# 8bitBusConcept.net
KiCad netlist of a schematic drawn in EAGLE
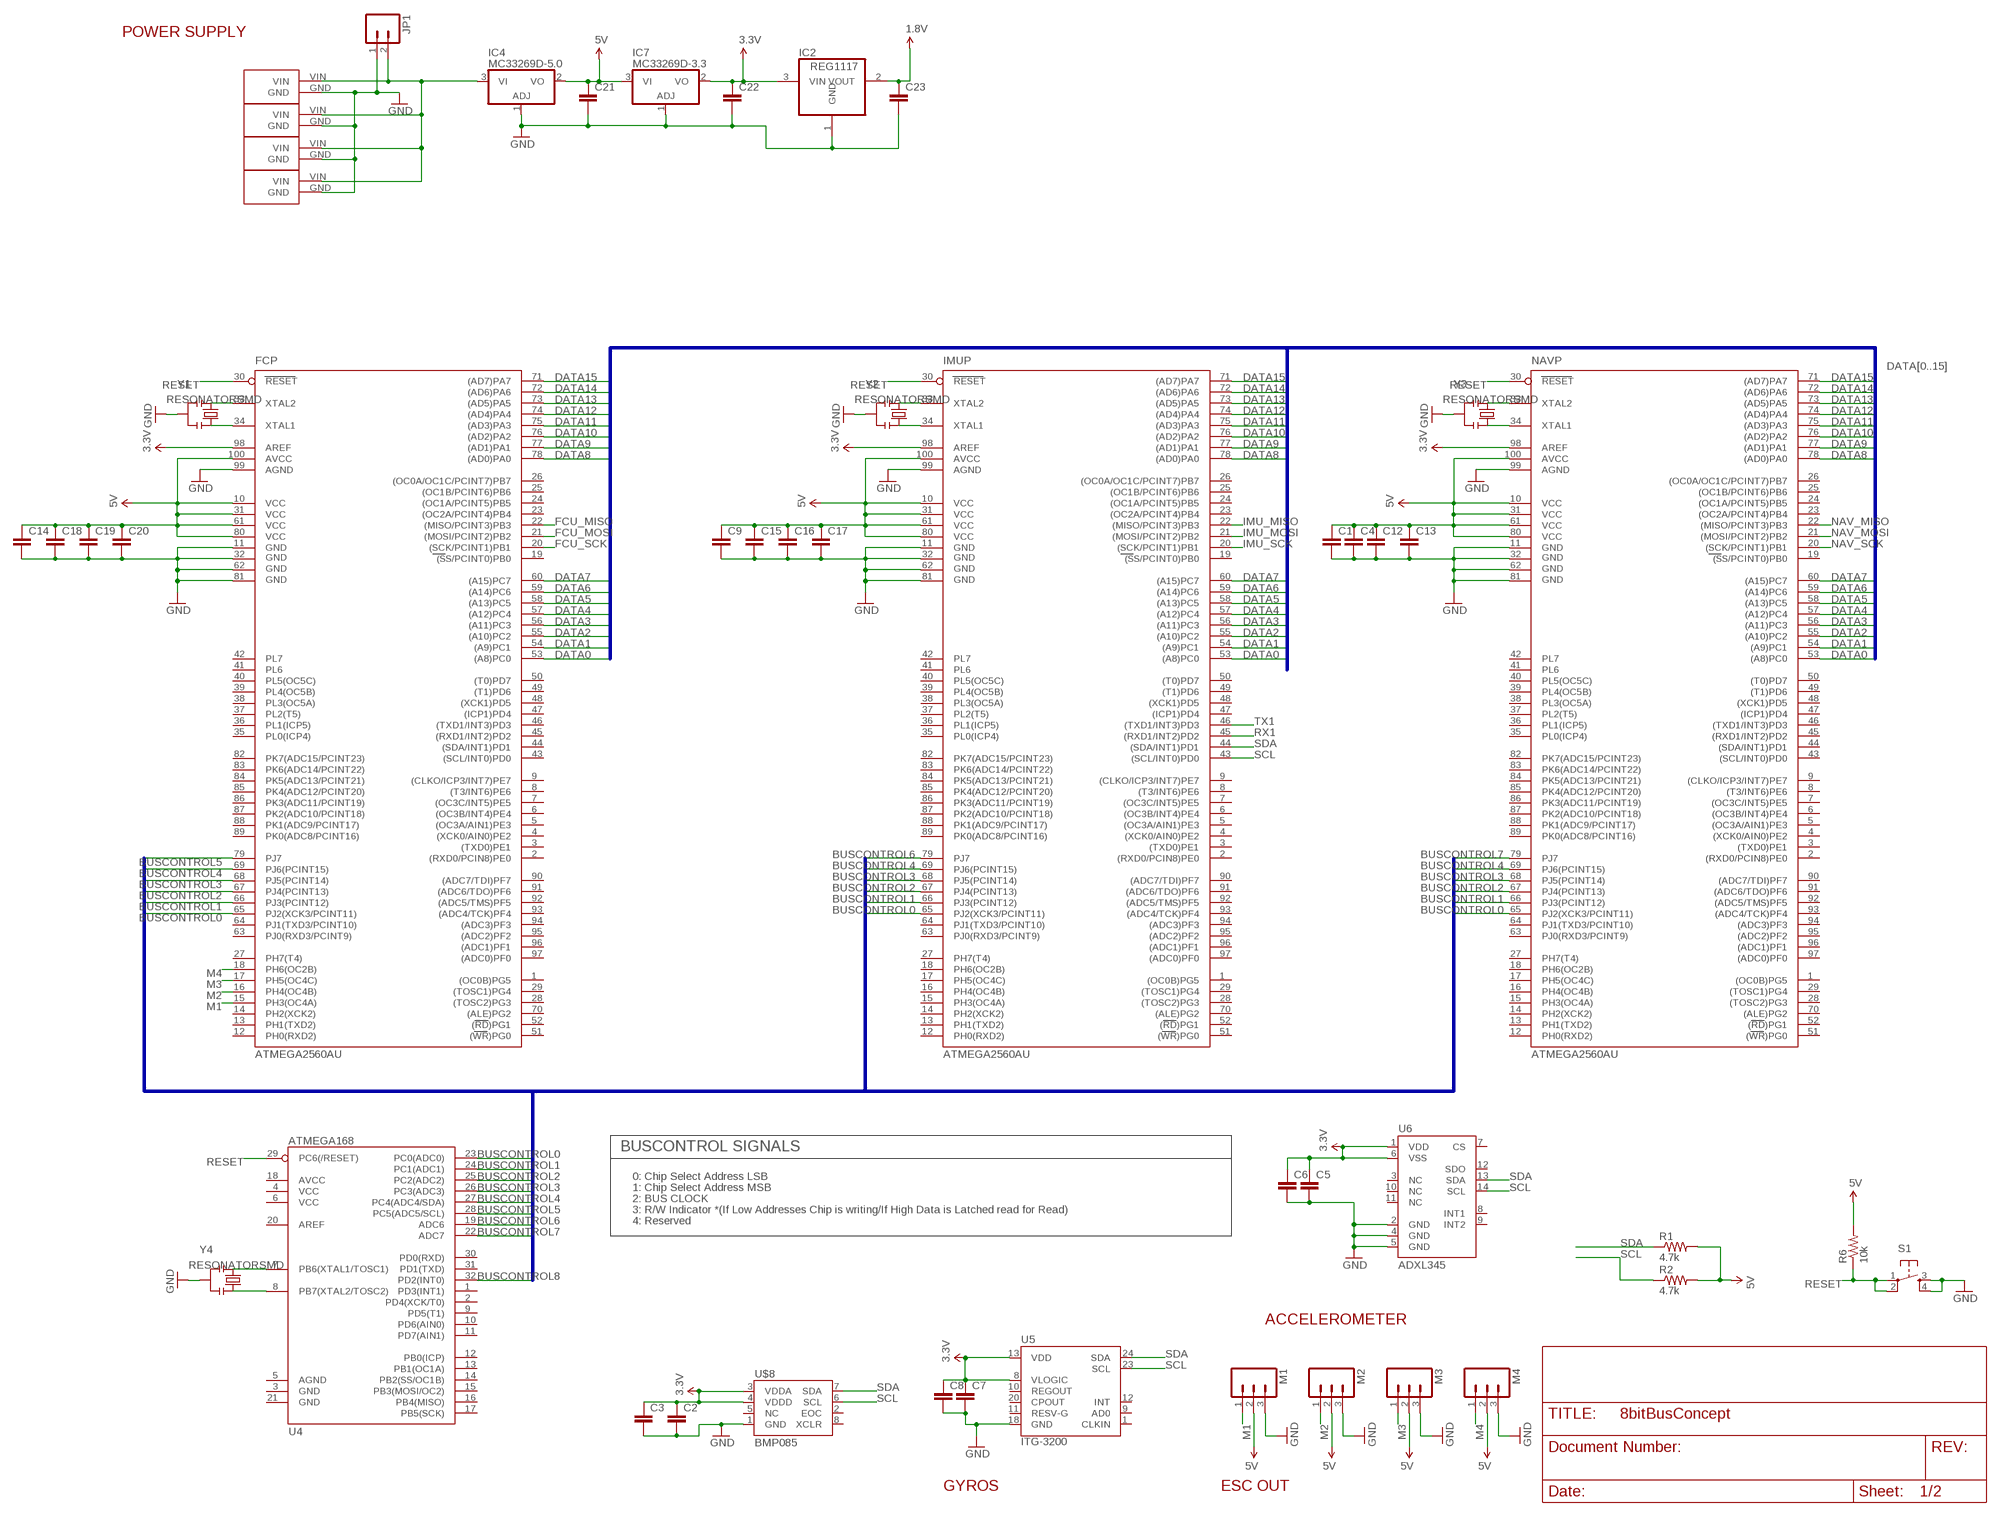
[diagram p0: schematic, sheet 1, part 1 of 2]
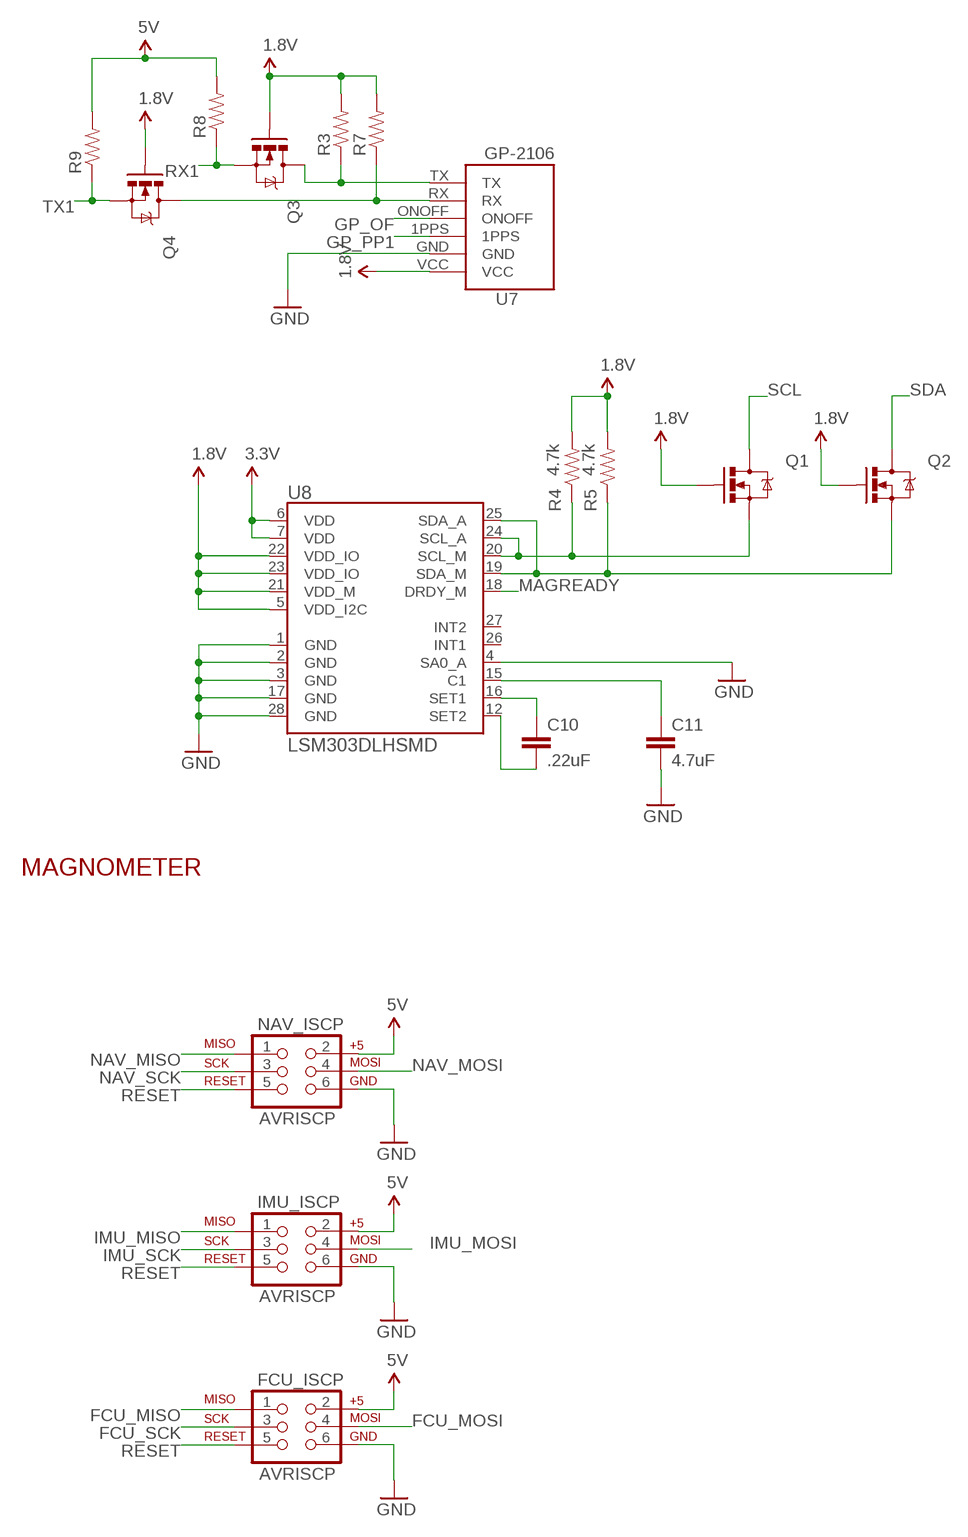
[diagram p1: schematic, sheet 1, part 2 of 2]

(export (version "E")
  (design (tool "Eeschema 10.0.6"))
  (components
    (comp (ref "C1")
      (value "CAP0805")
      (footprint "eagle-import:0805")
      (libsource (lib "eagle-import") (part "CAP0805"))
    )
    (comp (ref "C2")
      (value "CAP0805")
      (footprint "eagle-import:0805")
      (libsource (lib "eagle-import") (part "CAP0805"))
    )
    (comp (ref "C3")
      (value "CAP0805")
      (footprint "eagle-import:0805")
      (libsource (lib "eagle-import") (part "CAP0805"))
    )
    (comp (ref "C4")
      (value "CAP0805")
      (footprint "eagle-import:0805")
      (libsource (lib "eagle-import") (part "CAP0805"))
    )
    (comp (ref "C5")
      (value "CAP0805")
      (footprint "eagle-import:0805")
      (libsource (lib "eagle-import") (part "CAP0805"))
    )
    (comp (ref "C6")
      (value "CAP0805")
      (footprint "eagle-import:0805")
      (libsource (lib "eagle-import") (part "CAP0805"))
    )
    (comp (ref "C7")
      (value "CAP0805")
      (footprint "eagle-import:0805")
      (libsource (lib "eagle-import") (part "CAP0805"))
    )
    (comp (ref "C8")
      (value "CAP0805")
      (footprint "eagle-import:0805")
      (libsource (lib "eagle-import") (part "CAP0805"))
    )
    (comp (ref "C9")
      (value "CAP0805")
      (footprint "eagle-import:0805")
      (libsource (lib "eagle-import") (part "CAP0805"))
    )
    (comp (ref "C10")
      (value ".22uF")
      (footprint "eagle-import:0805")
      (libsource (lib "eagle-import") (part "CAP0805"))
    )
    (comp (ref "C11")
      (value "4.7uF")
      (footprint "eagle-import:0805")
      (libsource (lib "eagle-import") (part "CAP0805"))
    )
    (comp (ref "C12")
      (value "CAP0805")
      (footprint "eagle-import:0805")
      (libsource (lib "eagle-import") (part "CAP0805"))
    )
    (comp (ref "C13")
      (value "CAP0805")
      (footprint "eagle-import:0805")
      (libsource (lib "eagle-import") (part "CAP0805"))
    )
    (comp (ref "C14")
      (value "CAP0805")
      (footprint "eagle-import:0805")
      (libsource (lib "eagle-import") (part "CAP0805"))
    )
    (comp (ref "C15")
      (value "CAP0805")
      (footprint "eagle-import:0805")
      (libsource (lib "eagle-import") (part "CAP0805"))
    )
    (comp (ref "C16")
      (value "CAP0805")
      (footprint "eagle-import:0805")
      (libsource (lib "eagle-import") (part "CAP0805"))
    )
    (comp (ref "C17")
      (value "CAP0805")
      (footprint "eagle-import:0805")
      (libsource (lib "eagle-import") (part "CAP0805"))
    )
    (comp (ref "C18")
      (value "CAP0805")
      (footprint "eagle-import:0805")
      (libsource (lib "eagle-import") (part "CAP0805"))
    )
    (comp (ref "C19")
      (value "CAP0805")
      (footprint "eagle-import:0805")
      (libsource (lib "eagle-import") (part "CAP0805"))
    )
    (comp (ref "C20")
      (value "CAP0805")
      (footprint "eagle-import:0805")
      (libsource (lib "eagle-import") (part "CAP0805"))
    )
    (comp (ref "C21")
      (value "CAP0805")
      (footprint "eagle-import:0805")
      (libsource (lib "eagle-import") (part "CAP0805"))
    )
    (comp (ref "C22")
      (value "CAP0805")
      (footprint "eagle-import:0805")
      (libsource (lib "eagle-import") (part "CAP0805"))
    )
    (comp (ref "C23")
      (value "CAP0805")
      (footprint "eagle-import:0805")
      (libsource (lib "eagle-import") (part "CAP0805"))
    )
    (comp (ref "FCP")
      (value "ATMEGA2560AU")
      (footprint "eagle-import:TQFP100")
      (libsource (lib "eagle-import") (part "ATMEGA2560AU"))
    )
    (comp (ref "FCU_ISCP")
      (value "AVRISCP")
      (footprint "eagle-import:2X3")
      (libsource (lib "eagle-import") (part "AVR_SPI_PRG_6PTH"))
    )
    (comp (ref "IC2")
      (value "REG1117")
      (footprint "eagle-import:SOT223")
      (libsource (lib "eagle-import") (part "REG1117"))
    )
    (comp (ref "IC4")
      (value "MC33269D-5.0")
      (footprint "eagle-import:DPACK")
      (libsource (lib "eagle-import") (part "MC33269?D-5.0"))
    )
    (comp (ref "IC7")
      (value "MC33269D-3.3")
      (footprint "eagle-import:DPACK")
      (libsource (lib "eagle-import") (part "MC33269?D-3.3"))
    )
    (comp (ref "IMUP")
      (value "ATMEGA2560AU")
      (footprint "eagle-import:TQFP100")
      (libsource (lib "eagle-import") (part "ATMEGA2560AU"))
    )
    (comp (ref "IMU_ISCP")
      (value "AVRISCP")
      (footprint "eagle-import:2X3")
      (libsource (lib "eagle-import") (part "AVR_SPI_PRG_6PTH"))
    )
    (comp (ref "JP1")
      (value "M02PTH4")
      (footprint "eagle-import:1X02_XTRA_BIG")
      (libsource (lib "eagle-import") (part "M02PTH4"))
    )
    (comp (ref "M1")
      (value "M03PTH")
      (footprint "eagle-import:1X03")
      (libsource (lib "eagle-import") (part "M03PTH"))
    )
    (comp (ref "M2")
      (value "M03PTH")
      (footprint "eagle-import:1X03")
      (libsource (lib "eagle-import") (part "M03PTH"))
    )
    (comp (ref "M3")
      (value "M03PTH")
      (footprint "eagle-import:1X03")
      (libsource (lib "eagle-import") (part "M03PTH"))
    )
    (comp (ref "M4")
      (value "M03PTH")
      (footprint "eagle-import:1X03")
      (libsource (lib "eagle-import") (part "M03PTH"))
    )
    (comp (ref "NAVP")
      (value "ATMEGA2560AU")
      (footprint "eagle-import:TQFP100")
      (libsource (lib "eagle-import") (part "ATMEGA2560AU"))
    )
    (comp (ref "NAV_ISCP")
      (value "AVRISCP")
      (footprint "eagle-import:2X3")
      (libsource (lib "eagle-import") (part "AVR_SPI_PRG_6PTH"))
    )
    (comp (ref "Q1")
      (value "MOSFET-NCHANNELSMD")
      (footprint "eagle-import:SOT23-3")
      (libsource (lib "eagle-import") (part "MOSFET-NCHANNELSMD"))
    )
    (comp (ref "Q2")
      (value "MOSFET-NCHANNELSMD")
      (footprint "eagle-import:SOT23-3")
      (libsource (lib "eagle-import") (part "MOSFET-NCHANNELSMD"))
    )
    (comp (ref "Q3")
      (value "MOSFET-NCHANNELSMD")
      (footprint "eagle-import:SOT23-3")
      (libsource (lib "eagle-import") (part "MOSFET-NCHANNELSMD"))
    )
    (comp (ref "Q4")
      (value "MOSFET-NCHANNELSMD")
      (footprint "eagle-import:SOT23-3")
      (libsource (lib "eagle-import") (part "MOSFET-NCHANNELSMD"))
    )
    (comp (ref "R1")
      (value "4.7k")
      (footprint "eagle-import:0805")
      (libsource (lib "eagle-import") (part "RESISTOR0805-RES"))
    )
    (comp (ref "R2")
      (value "4.7k")
      (footprint "eagle-import:0805")
      (libsource (lib "eagle-import") (part "RESISTOR0805-RES"))
    )
    (comp (ref "R3")
      (value "RESISTOR0805-RES")
      (footprint "eagle-import:0805")
      (libsource (lib "eagle-import") (part "RESISTOR0805-RES"))
    )
    (comp (ref "R4")
      (value "4.7k")
      (footprint "eagle-import:0805")
      (libsource (lib "eagle-import") (part "RESISTOR0805-RES"))
    )
    (comp (ref "R5")
      (value "4.7k")
      (footprint "eagle-import:0805")
      (libsource (lib "eagle-import") (part "RESISTOR0805-RES"))
    )
    (comp (ref "R6")
      (value "10k")
      (footprint "eagle-import:0805")
      (libsource (lib "eagle-import") (part "RESISTOR0805-RES"))
    )
    (comp (ref "R7")
      (value "RESISTOR0805-RES")
      (footprint "eagle-import:0805")
      (libsource (lib "eagle-import") (part "RESISTOR0805-RES"))
    )
    (comp (ref "R8")
      (value "RESISTOR0805-RES")
      (footprint "eagle-import:0805")
      (libsource (lib "eagle-import") (part "RESISTOR0805-RES"))
    )
    (comp (ref "R9")
      (value "RESISTOR0805-RES")
      (footprint "eagle-import:0805")
      (libsource (lib "eagle-import") (part "RESISTOR0805-RES"))
    )
    (comp (ref "S1")
      (value "TAC_SWITCHSMD")
      (footprint "eagle-import:TACTILE_SWITCH_SMD")
      (libsource (lib "eagle-import") (part "TAC_SWITCHSMD"))
    )
    (comp (ref "U$8")
      (value "BMP085")
      (footprint "eagle-import:BMP085")
      (libsource (lib "eagle-import") (part "BMP085"))
    )
    (comp (ref "U$24")
      (value "ESC_POWER")
      (footprint "eagle-import:ESCPOWER")
      (libsource (lib "eagle-import") (part "ESC_POWER"))
    )
    (comp (ref "U$25")
      (value "ESC_POWER")
      (footprint "eagle-import:ESCPOWER")
      (libsource (lib "eagle-import") (part "ESC_POWER"))
    )
    (comp (ref "U$26")
      (value "ESC_POWER")
      (footprint "eagle-import:ESCPOWER")
      (libsource (lib "eagle-import") (part "ESC_POWER"))
    )
    (comp (ref "U$27")
      (value "ESC_POWER")
      (footprint "eagle-import:ESCPOWER")
      (libsource (lib "eagle-import") (part "ESC_POWER"))
    )
    (comp (ref "U4")
      (value "ATMEGA168")
      (footprint "eagle-import:TQFP32-08")
      (libsource (lib "eagle-import") (part "ATMEGA168"))
    )
    (comp (ref "U5")
      (value "ITG-3200")
      (footprint "eagle-import:QFN-24")
      (libsource (lib "eagle-import") (part "ITG-3200"))
    )
    (comp (ref "U6")
      (value "ADXL345")
      (footprint "eagle-import:LGA14")
      (libsource (lib "eagle-import") (part "ADXL345"))
    )
    (comp (ref "U7")
      (value "GP-2106")
      (footprint "eagle-import:GP-2106")
      (libsource (lib "eagle-import") (part "GP-2106"))
    )
    (comp (ref "U8")
      (value "LSM303DLHSMD")
      (footprint "eagle-import:LGA28-5X5")
      (libsource (lib "eagle-import") (part "LSM303DLHSMD"))
    )
    (comp (ref "Y1")
      (value "RESONATORSMD")
      (footprint "eagle-import:RESONATOR-SMD")
      (libsource (lib "eagle-import") (part "RESONATORSMD"))
    )
    (comp (ref "Y2")
      (value "RESONATORSMD")
      (footprint "eagle-import:RESONATOR-SMD")
      (libsource (lib "eagle-import") (part "RESONATORSMD"))
    )
    (comp (ref "Y3")
      (value "RESONATORSMD")
      (footprint "eagle-import:RESONATOR-SMD")
      (libsource (lib "eagle-import") (part "RESONATORSMD"))
    )
    (comp (ref "Y4")
      (value "RESONATORSMD")
      (footprint "eagle-import:RESONATOR-SMD")
      (libsource (lib "eagle-import") (part "RESONATORSMD"))
    )
  )
  (nets
    (net (code "2") (name "1.8V") (class "Default")
      (node (ref "C23") (pin "1") (pinfunction "1_1") (pintype "passive"))
      (node (ref "IC2") (pin "2") (pinfunction "VOUT_2") (pintype "output"))
      (node (ref "Q1") (pin "1") (pinfunction "G_1") (pintype "passive"))
      (node (ref "Q2") (pin "1") (pinfunction "G_1") (pintype "passive"))
      (node (ref "Q3") (pin "1") (pinfunction "G_1") (pintype "passive"))
      (node (ref "Q4") (pin "1") (pinfunction "G_1") (pintype "passive"))
      (node (ref "R3") (pin "2") (pinfunction "2_2") (pintype "passive"))
      (node (ref "R4") (pin "2") (pinfunction "2_2") (pintype "passive"))
      (node (ref "R5") (pin "2") (pinfunction "2_2") (pintype "passive"))
      (node (ref "R7") (pin "2") (pinfunction "2_2") (pintype "passive"))
      (node (ref "U7") (pin "VCC") (pinfunction "VCC_VCC") (pintype "bidirectional"))
      (node (ref "U8") (pin "21") (pinfunction "VDD_M_21") (pintype "bidirectional"))
      (node (ref "U8") (pin "22") (pinfunction "VDD_IO_22") (pintype "bidirectional"))
      (node (ref "U8") (pin "23") (pinfunction "VDD_IO_23") (pintype "bidirectional"))
      (node (ref "U8") (pin "5") (pinfunction "VDD_I2C_5") (pintype "bidirectional"))
    )
    (net (code "3") (name "3.3V") (class "Default")
      (node (ref "C2") (pin "1") (pinfunction "1_1") (pintype "passive"))
      (node (ref "C22") (pin "1") (pinfunction "1_1") (pintype "passive"))
      (node (ref "C3") (pin "1") (pinfunction "1_1") (pintype "passive"))
      (node (ref "C5") (pin "1") (pinfunction "1_1") (pintype "passive"))
      (node (ref "C6") (pin "1") (pinfunction "1_1") (pintype "passive"))
      (node (ref "C7") (pin "1") (pinfunction "1_1") (pintype "passive"))
      (node (ref "C8") (pin "1") (pinfunction "1_1") (pintype "passive"))
      (node (ref "FCP") (pin "98") (pinfunction "AREF_98") (pintype "bidirectional"))
      (node (ref "IC2") (pin "3") (pinfunction "VIN_3") (pintype "input"))
      (node (ref "IC7") (pin "2") (pinfunction "VO_2") (pintype "passive"))
      (node (ref "IMUP") (pin "98") (pinfunction "AREF_98") (pintype "bidirectional"))
      (node (ref "NAVP") (pin "98") (pinfunction "AREF_98") (pintype "bidirectional"))
      (node (ref "U$8") (pin "3") (pinfunction "VDDA_3") (pintype "power_in"))
      (node (ref "U$8") (pin "4") (pinfunction "VDDD_4") (pintype "power_in"))
      (node (ref "U5") (pin "13") (pinfunction "VDD_13") (pintype "bidirectional"))
      (node (ref "U5") (pin "8") (pinfunction "VLOGIC_8") (pintype "bidirectional"))
      (node (ref "U6") (pin "1") (pinfunction "VDD_1") (pintype "bidirectional"))
      (node (ref "U6") (pin "6") (pinfunction "VSS_6") (pintype "bidirectional"))
      (node (ref "U8") (pin "6") (pinfunction "VDD_6") (pintype "bidirectional"))
      (node (ref "U8") (pin "7") (pinfunction "VDD_7") (pintype "bidirectional"))
    )
    (net (code "4") (name "5V") (class "Default")
      (node (ref "C1") (pin "1") (pinfunction "1_1") (pintype "passive"))
      (node (ref "C12") (pin "1") (pinfunction "1_1") (pintype "passive"))
      (node (ref "C13") (pin "1") (pinfunction "1_1") (pintype "passive"))
      (node (ref "C14") (pin "1") (pinfunction "1_1") (pintype "passive"))
      (node (ref "C15") (pin "1") (pinfunction "1_1") (pintype "passive"))
      (node (ref "C16") (pin "1") (pinfunction "1_1") (pintype "passive"))
      (node (ref "C17") (pin "1") (pinfunction "1_1") (pintype "passive"))
      (node (ref "C18") (pin "1") (pinfunction "1_1") (pintype "passive"))
      (node (ref "C19") (pin "1") (pinfunction "1_1") (pintype "passive"))
      (node (ref "C20") (pin "1") (pinfunction "1_1") (pintype "passive"))
      (node (ref "C21") (pin "1") (pinfunction "1_1") (pintype "passive"))
      (node (ref "C4") (pin "1") (pinfunction "1_1") (pintype "passive"))
      (node (ref "C9") (pin "1") (pinfunction "1_1") (pintype "passive"))
      (node (ref "FCP") (pin "10") (pinfunction "VCC_10") (pintype "power_in"))
      (node (ref "FCP") (pin "100") (pinfunction "AVCC_100") (pintype "power_in"))
      (node (ref "FCP") (pin "31") (pinfunction "VCC1_31") (pintype "power_in"))
      (node (ref "FCP") (pin "61") (pinfunction "VCC2_61") (pintype "power_in"))
      (node (ref "FCP") (pin "80") (pinfunction "VCC3_80") (pintype "power_in"))
      (node (ref "FCU_ISCP") (pin "2") (pinfunction "2_2") (pintype "passive"))
      (node (ref "IC4") (pin "2") (pinfunction "VO_2") (pintype "passive"))
      (node (ref "IC7") (pin "3") (pinfunction "VI_3") (pintype "input"))
      (node (ref "IMUP") (pin "10") (pinfunction "VCC_10") (pintype "power_in"))
      (node (ref "IMUP") (pin "100") (pinfunction "AVCC_100") (pintype "power_in"))
      (node (ref "IMUP") (pin "31") (pinfunction "VCC1_31") (pintype "power_in"))
      (node (ref "IMUP") (pin "61") (pinfunction "VCC2_61") (pintype "power_in"))
      (node (ref "IMUP") (pin "80") (pinfunction "VCC3_80") (pintype "power_in"))
      (node (ref "IMU_ISCP") (pin "2") (pinfunction "2_2") (pintype "passive"))
      (node (ref "M1") (pin "2") (pinfunction "2_2") (pintype "passive"))
      (node (ref "M2") (pin "2") (pinfunction "2_2") (pintype "passive"))
      (node (ref "M3") (pin "2") (pinfunction "2_2") (pintype "passive"))
      (node (ref "M4") (pin "2") (pinfunction "2_2") (pintype "passive"))
      (node (ref "NAVP") (pin "10") (pinfunction "VCC_10") (pintype "power_in"))
      (node (ref "NAVP") (pin "100") (pinfunction "AVCC_100") (pintype "power_in"))
      (node (ref "NAVP") (pin "31") (pinfunction "VCC1_31") (pintype "power_in"))
      (node (ref "NAVP") (pin "61") (pinfunction "VCC2_61") (pintype "power_in"))
      (node (ref "NAVP") (pin "80") (pinfunction "VCC3_80") (pintype "power_in"))
      (node (ref "NAV_ISCP") (pin "2") (pinfunction "2_2") (pintype "passive"))
      (node (ref "R1") (pin "2") (pinfunction "2_2") (pintype "passive"))
      (node (ref "R2") (pin "2") (pinfunction "2_2") (pintype "passive"))
      (node (ref "R6") (pin "2") (pinfunction "2_2") (pintype "passive"))
      (node (ref "R8") (pin "2") (pinfunction "2_2") (pintype "passive"))
      (node (ref "R9") (pin "2") (pinfunction "2_2") (pintype "passive"))
    )
    (net (code "5") (name "BUSCONTROL0") (class "Default")
      (node (ref "FCP") (pin "65") (pinfunction "PJ2(XCK3/PCINT11)_65") (pintype "bidirectional"))
      (node (ref "IMUP") (pin "65") (pinfunction "PJ2(XCK3/PCINT11)_65") (pintype "bidirectional"))
      (node (ref "NAVP") (pin "65") (pinfunction "PJ2(XCK3/PCINT11)_65") (pintype "bidirectional"))
      (node (ref "U4") (pin "23") (pinfunction "PC0(ADC0)_23") (pintype "bidirectional"))
    )
    (net (code "6") (name "BUSCONTROL1") (class "Default")
      (node (ref "FCP") (pin "66") (pinfunction "PJ3(PCINT12)_66") (pintype "bidirectional"))
      (node (ref "IMUP") (pin "66") (pinfunction "PJ3(PCINT12)_66") (pintype "bidirectional"))
      (node (ref "NAVP") (pin "66") (pinfunction "PJ3(PCINT12)_66") (pintype "bidirectional"))
      (node (ref "U4") (pin "24") (pinfunction "PC1(ADC1)_24") (pintype "bidirectional"))
    )
    (net (code "7") (name "BUSCONTROL2") (class "Default")
      (node (ref "FCP") (pin "67") (pinfunction "PJ4(PCINT13)_67") (pintype "bidirectional"))
      (node (ref "IMUP") (pin "67") (pinfunction "PJ4(PCINT13)_67") (pintype "bidirectional"))
      (node (ref "NAVP") (pin "67") (pinfunction "PJ4(PCINT13)_67") (pintype "bidirectional"))
      (node (ref "U4") (pin "25") (pinfunction "PC2(ADC2)_25") (pintype "bidirectional"))
    )
    (net (code "8") (name "BUSCONTROL3") (class "Default")
      (node (ref "FCP") (pin "68") (pinfunction "PJ5(PCINT14)_68") (pintype "bidirectional"))
      (node (ref "IMUP") (pin "68") (pinfunction "PJ5(PCINT14)_68") (pintype "bidirectional"))
      (node (ref "NAVP") (pin "68") (pinfunction "PJ5(PCINT14)_68") (pintype "bidirectional"))
      (node (ref "U4") (pin "26") (pinfunction "PC3(ADC3)_26") (pintype "bidirectional"))
    )
    (net (code "9") (name "BUSCONTROL4") (class "Default")
      (node (ref "FCP") (pin "69") (pinfunction "PJ6(PCINT15)_69") (pintype "bidirectional"))
      (node (ref "IMUP") (pin "69") (pinfunction "PJ6(PCINT15)_69") (pintype "bidirectional"))
      (node (ref "NAVP") (pin "69") (pinfunction "PJ6(PCINT15)_69") (pintype "bidirectional"))
      (node (ref "U4") (pin "27") (pinfunction "PC4(ADC4/SDA)_27") (pintype "bidirectional"))
    )
    (net (code "10") (name "BUSCONTROL5") (class "Default")
      (node (ref "FCP") (pin "79") (pinfunction "PJ7_79") (pintype "bidirectional"))
      (node (ref "U4") (pin "28") (pinfunction "PC5(ADC5/SCL)_28") (pintype "bidirectional"))
    )
    (net (code "11") (name "BUSCONTROL6") (class "Default")
      (node (ref "IMUP") (pin "79") (pinfunction "PJ7_79") (pintype "bidirectional"))
      (node (ref "U4") (pin "19") (pinfunction "ADC6_19") (pintype "bidirectional"))
    )
    (net (code "12") (name "BUSCONTROL7") (class "Default")
      (node (ref "NAVP") (pin "79") (pinfunction "PJ7_79") (pintype "bidirectional"))
      (node (ref "U4") (pin "22") (pinfunction "ADC7_22") (pintype "bidirectional"))
    )
    (net (code "13") (name "BUSCONTROL8") (class "Default")
      (node (ref "U4") (pin "32") (pinfunction "PD2(INT0)_32") (pintype "bidirectional"))
    )
    (net (code "14") (name "DATA0") (class "Default")
      (node (ref "FCP") (pin "53") (pinfunction "(A8)PC0_53") (pintype "bidirectional"))
      (node (ref "IMUP") (pin "53") (pinfunction "(A8)PC0_53") (pintype "bidirectional"))
      (node (ref "NAVP") (pin "53") (pinfunction "(A8)PC0_53") (pintype "bidirectional"))
    )
    (net (code "15") (name "DATA1") (class "Default")
      (node (ref "FCP") (pin "54") (pinfunction "(A9)PC1_54") (pintype "bidirectional"))
      (node (ref "IMUP") (pin "54") (pinfunction "(A9)PC1_54") (pintype "bidirectional"))
      (node (ref "NAVP") (pin "54") (pinfunction "(A9)PC1_54") (pintype "bidirectional"))
    )
    (net (code "16") (name "DATA2") (class "Default")
      (node (ref "FCP") (pin "55") (pinfunction "(A10)PC2_55") (pintype "bidirectional"))
      (node (ref "IMUP") (pin "55") (pinfunction "(A10)PC2_55") (pintype "bidirectional"))
      (node (ref "NAVP") (pin "55") (pinfunction "(A10)PC2_55") (pintype "bidirectional"))
    )
    (net (code "17") (name "DATA3") (class "Default")
      (node (ref "FCP") (pin "56") (pinfunction "(A11)PC3_56") (pintype "bidirectional"))
      (node (ref "IMUP") (pin "56") (pinfunction "(A11)PC3_56") (pintype "bidirectional"))
      (node (ref "NAVP") (pin "56") (pinfunction "(A11)PC3_56") (pintype "bidirectional"))
    )
    (net (code "18") (name "DATA4") (class "Default")
      (node (ref "FCP") (pin "57") (pinfunction "(A12)PC4_57") (pintype "bidirectional"))
      (node (ref "IMUP") (pin "57") (pinfunction "(A12)PC4_57") (pintype "bidirectional"))
      (node (ref "NAVP") (pin "57") (pinfunction "(A12)PC4_57") (pintype "bidirectional"))
    )
    (net (code "19") (name "DATA5") (class "Default")
      (node (ref "FCP") (pin "58") (pinfunction "(A13)PC5_58") (pintype "bidirectional"))
      (node (ref "IMUP") (pin "58") (pinfunction "(A13)PC5_58") (pintype "bidirectional"))
      (node (ref "NAVP") (pin "58") (pinfunction "(A13)PC5_58") (pintype "bidirectional"))
    )
    (net (code "20") (name "DATA6") (class "Default")
      (node (ref "FCP") (pin "59") (pinfunction "(A14)PC6_59") (pintype "bidirectional"))
      (node (ref "IMUP") (pin "59") (pinfunction "(A14)PC6_59") (pintype "bidirectional"))
      (node (ref "NAVP") (pin "59") (pinfunction "(A14)PC6_59") (pintype "bidirectional"))
    )
    (net (code "21") (name "DATA7") (class "Default")
      (node (ref "FCP") (pin "60") (pinfunction "(A15)PC7_60") (pintype "bidirectional"))
      (node (ref "IMUP") (pin "60") (pinfunction "(A15)PC7_60") (pintype "bidirectional"))
      (node (ref "NAVP") (pin "60") (pinfunction "(A15)PC7_60") (pintype "bidirectional"))
    )
    (net (code "22") (name "DATA8") (class "Default")
      (node (ref "FCP") (pin "78") (pinfunction "(AD0)PA0_78") (pintype "bidirectional"))
      (node (ref "IMUP") (pin "78") (pinfunction "(AD0)PA0_78") (pintype "bidirectional"))
      (node (ref "NAVP") (pin "78") (pinfunction "(AD0)PA0_78") (pintype "bidirectional"))
    )
    (net (code "23") (name "DATA9") (class "Default")
      (node (ref "FCP") (pin "77") (pinfunction "(AD1)PA1_77") (pintype "bidirectional"))
      (node (ref "IMUP") (pin "77") (pinfunction "(AD1)PA1_77") (pintype "bidirectional"))
      (node (ref "NAVP") (pin "77") (pinfunction "(AD1)PA1_77") (pintype "bidirectional"))
    )
    (net (code "24") (name "DATA10") (class "Default")
      (node (ref "FCP") (pin "76") (pinfunction "(AD2)PA2_76") (pintype "bidirectional"))
      (node (ref "IMUP") (pin "76") (pinfunction "(AD2)PA2_76") (pintype "bidirectional"))
      (node (ref "NAVP") (pin "76") (pinfunction "(AD2)PA2_76") (pintype "bidirectional"))
    )
    (net (code "25") (name "DATA11") (class "Default")
      (node (ref "FCP") (pin "75") (pinfunction "(AD3)PA3_75") (pintype "bidirectional"))
      (node (ref "IMUP") (pin "75") (pinfunction "(AD3)PA3_75") (pintype "bidirectional"))
      (node (ref "NAVP") (pin "75") (pinfunction "(AD3)PA3_75") (pintype "bidirectional"))
    )
    (net (code "26") (name "DATA12") (class "Default")
      (node (ref "FCP") (pin "74") (pinfunction "(AD4)PA4_74") (pintype "bidirectional"))
      (node (ref "IMUP") (pin "74") (pinfunction "(AD4)PA4_74") (pintype "bidirectional"))
      (node (ref "NAVP") (pin "74") (pinfunction "(AD4)PA4_74") (pintype "bidirectional"))
    )
    (net (code "27") (name "DATA13") (class "Default")
      (node (ref "FCP") (pin "73") (pinfunction "(AD5)PA5_73") (pintype "bidirectional"))
      (node (ref "IMUP") (pin "73") (pinfunction "(AD5)PA5_73") (pintype "bidirectional"))
      (node (ref "NAVP") (pin "73") (pinfunction "(AD5)PA5_73") (pintype "bidirectional"))
    )
    (net (code "28") (name "DATA14") (class "Default")
      (node (ref "FCP") (pin "72") (pinfunction "(AD6)PA6_72") (pintype "bidirectional"))
      (node (ref "IMUP") (pin "72") (pinfunction "(AD6)PA6_72") (pintype "bidirectional"))
      (node (ref "NAVP") (pin "72") (pinfunction "(AD6)PA6_72") (pintype "bidirectional"))
    )
    (net (code "29") (name "DATA15") (class "Default")
      (node (ref "FCP") (pin "71") (pinfunction "(AD7)PA7_71") (pintype "bidirectional"))
      (node (ref "IMUP") (pin "71") (pinfunction "(AD7)PA7_71") (pintype "bidirectional"))
      (node (ref "NAVP") (pin "71") (pinfunction "(AD7)PA7_71") (pintype "bidirectional"))
    )
    (net (code "30") (name "FCU_MISO") (class "Default")
      (node (ref "FCP") (pin "22") (pinfunction "(MISO/PCINT3)PB3_22") (pintype "bidirectional"))
      (node (ref "FCU_ISCP") (pin "1") (pinfunction "1_1") (pintype "passive"))
    )
    (net (code "31") (name "FCU_MOSI") (class "Default")
      (node (ref "FCP") (pin "21") (pinfunction "(MOSI/PCINT2)PB2_21") (pintype "bidirectional"))
      (node (ref "FCU_ISCP") (pin "4") (pinfunction "4_4") (pintype "passive"))
    )
    (net (code "32") (name "FCU_SCK") (class "Default")
      (node (ref "FCP") (pin "20") (pinfunction "(SCK/PCINT1)PB1_20") (pintype "bidirectional"))
      (node (ref "FCU_ISCP") (pin "3") (pinfunction "3_3") (pintype "passive"))
    )
    (net (code "33") (name "GND") (class "Default")
      (node (ref "C1") (pin "2") (pinfunction "2_2") (pintype "passive"))
      (node (ref "C11") (pin "2") (pinfunction "2_2") (pintype "passive"))
      (node (ref "C12") (pin "2") (pinfunction "2_2") (pintype "passive"))
      (node (ref "C13") (pin "2") (pinfunction "2_2") (pintype "passive"))
      (node (ref "C14") (pin "2") (pinfunction "2_2") (pintype "passive"))
      (node (ref "C15") (pin "2") (pinfunction "2_2") (pintype "passive"))
      (node (ref "C16") (pin "2") (pinfunction "2_2") (pintype "passive"))
      (node (ref "C17") (pin "2") (pinfunction "2_2") (pintype "passive"))
      (node (ref "C18") (pin "2") (pinfunction "2_2") (pintype "passive"))
      (node (ref "C19") (pin "2") (pinfunction "2_2") (pintype "passive"))
      (node (ref "C2") (pin "2") (pinfunction "2_2") (pintype "passive"))
      (node (ref "C20") (pin "2") (pinfunction "2_2") (pintype "passive"))
      (node (ref "C21") (pin "2") (pinfunction "2_2") (pintype "passive"))
      (node (ref "C22") (pin "2") (pinfunction "2_2") (pintype "passive"))
      (node (ref "C23") (pin "2") (pinfunction "2_2") (pintype "passive"))
      (node (ref "C3") (pin "2") (pinfunction "2_2") (pintype "passive"))
      (node (ref "C4") (pin "2") (pinfunction "2_2") (pintype "passive"))
      (node (ref "C5") (pin "2") (pinfunction "2_2") (pintype "passive"))
      (node (ref "C6") (pin "2") (pinfunction "2_2") (pintype "passive"))
      (node (ref "C7") (pin "2") (pinfunction "2_2") (pintype "passive"))
      (node (ref "C8") (pin "2") (pinfunction "2_2") (pintype "passive"))
      (node (ref "C9") (pin "2") (pinfunction "2_2") (pintype "passive"))
      (node (ref "FCP") (pin "11") (pinfunction "GND_11") (pintype "power_in"))
      (node (ref "FCP") (pin "32") (pinfunction "GND1_32") (pintype "power_in"))
      (node (ref "FCP") (pin "62") (pinfunction "GND2_62") (pintype "power_in"))
      (node (ref "FCP") (pin "81") (pinfunction "GND3_81") (pintype "power_in"))
      (node (ref "FCP") (pin "99") (pinfunction "AGND_99") (pintype "power_in"))
      (node (ref "FCU_ISCP") (pin "6") (pinfunction "6_6") (pintype "passive"))
      (node (ref "IC2") (pin "1") (pinfunction "GND_1") (pintype "power_in"))
      (node (ref "IC4") (pin "1") (pinfunction "ADJ_1") (pintype "input"))
      (node (ref "IC7") (pin "1") (pinfunction "ADJ_1") (pintype "input"))
      (node (ref "IMUP") (pin "11") (pinfunction "GND_11") (pintype "power_in"))
      (node (ref "IMUP") (pin "32") (pinfunction "GND1_32") (pintype "power_in"))
      (node (ref "IMUP") (pin "62") (pinfunction "GND2_62") (pintype "power_in"))
      (node (ref "IMUP") (pin "81") (pinfunction "GND3_81") (pintype "power_in"))
      (node (ref "IMUP") (pin "99") (pinfunction "AGND_99") (pintype "power_in"))
      (node (ref "IMU_ISCP") (pin "6") (pinfunction "6_6") (pintype "passive"))
      (node (ref "JP1") (pin "1") (pinfunction "1_1") (pintype "passive"))
      (node (ref "M1") (pin "3") (pinfunction "3_3") (pintype "passive"))
      (node (ref "M2") (pin "3") (pinfunction "3_3") (pintype "passive"))
      (node (ref "M3") (pin "3") (pinfunction "3_3") (pintype "passive"))
      (node (ref "M4") (pin "3") (pinfunction "3_3") (pintype "passive"))
      (node (ref "NAVP") (pin "11") (pinfunction "GND_11") (pintype "power_in"))
      (node (ref "NAVP") (pin "32") (pinfunction "GND1_32") (pintype "power_in"))
      (node (ref "NAVP") (pin "62") (pinfunction "GND2_62") (pintype "power_in"))
      (node (ref "NAVP") (pin "81") (pinfunction "GND3_81") (pintype "power_in"))
      (node (ref "NAVP") (pin "99") (pinfunction "AGND_99") (pintype "power_in"))
      (node (ref "NAV_ISCP") (pin "6") (pinfunction "6_6") (pintype "passive"))
      (node (ref "S1") (pin "3") (pinfunction "3_3") (pintype "passive"))
      (node (ref "S1") (pin "4") (pinfunction "4_4") (pintype "passive"))
      (node (ref "U$24") (pin "GND") (pinfunction "GND_GND") (pintype "bidirectional"))
      (node (ref "U$25") (pin "GND") (pinfunction "GND_GND") (pintype "bidirectional"))
      (node (ref "U$26") (pin "GND") (pinfunction "GND_GND") (pintype "bidirectional"))
      (node (ref "U$27") (pin "GND") (pinfunction "GND_GND") (pintype "bidirectional"))
      (node (ref "U$8") (pin "1") (pinfunction "GND_1") (pintype "power_in"))
      (node (ref "U5") (pin "18") (pinfunction "GND_18") (pintype "bidirectional"))
      (node (ref "U6") (pin "2") (pinfunction "GND_2") (pintype "bidirectional"))
      (node (ref "U6") (pin "4") (pinfunction "GND_4") (pintype "bidirectional"))
      (node (ref "U6") (pin "5") (pinfunction "GND_5") (pintype "bidirectional"))
      (node (ref "U7") (pin "GND") (pinfunction "GND_GND") (pintype "bidirectional"))
      (node (ref "U8") (pin "1") (pinfunction "GND_1") (pintype "bidirectional"))
      (node (ref "U8") (pin "17") (pinfunction "GND_17") (pintype "bidirectional"))
      (node (ref "U8") (pin "2") (pinfunction "GND_2") (pintype "bidirectional"))
      (node (ref "U8") (pin "28") (pinfunction "GND_28") (pintype "bidirectional"))
      (node (ref "U8") (pin "3") (pinfunction "GND_3") (pintype "bidirectional"))
      (node (ref "U8") (pin "4") (pinfunction "SA0_A_4") (pintype "bidirectional"))
      (node (ref "Y1") (pin "2") (pinfunction "2_2") (pintype "passive"))
      (node (ref "Y2") (pin "2") (pinfunction "2_2") (pintype "passive"))
      (node (ref "Y3") (pin "2") (pinfunction "2_2") (pintype "passive"))
      (node (ref "Y4") (pin "2") (pinfunction "2_2") (pintype "passive"))
    )
    (net (code "34") (name "GP_OF") (class "Default")
      (node (ref "U7") (pin "ONOFF") (pinfunction "ONOFF_ONOFF") (pintype "bidirectional"))
    )
    (net (code "35") (name "GP_PP1") (class "Default")
      (node (ref "U7") (pin "1PPS") (pinfunction "1PPS_1PPS") (pintype "bidirectional"))
    )
    (net (code "36") (name "IMU_MISO") (class "Default")
      (node (ref "IMUP") (pin "22") (pinfunction "(MISO/PCINT3)PB3_22") (pintype "bidirectional"))
      (node (ref "IMU_ISCP") (pin "1") (pinfunction "1_1") (pintype "passive"))
    )
    (net (code "37") (name "IMU_MOSI") (class "Default")
      (node (ref "IMUP") (pin "21") (pinfunction "(MOSI/PCINT2)PB2_21") (pintype "bidirectional"))
      (node (ref "IMU_ISCP") (pin "4") (pinfunction "4_4") (pintype "passive"))
    )
    (net (code "38") (name "IMU_SCK") (class "Default")
      (node (ref "IMUP") (pin "20") (pinfunction "(SCK/PCINT1)PB1_20") (pintype "bidirectional"))
      (node (ref "IMU_ISCP") (pin "3") (pinfunction "3_3") (pintype "passive"))
    )
    (net (code "39") (name "M1") (class "Default")
      (node (ref "FCP") (pin "15") (pinfunction "PH3(OC4A)_15") (pintype "bidirectional"))
      (node (ref "M1") (pin "1") (pinfunction "1_1") (pintype "passive"))
    )
    (net (code "40") (name "M2") (class "Default")
      (node (ref "FCP") (pin "16") (pinfunction "PH4(OC4B)_16") (pintype "bidirectional"))
      (node (ref "M2") (pin "1") (pinfunction "1_1") (pintype "passive"))
    )
    (net (code "41") (name "M3") (class "Default")
      (node (ref "FCP") (pin "17") (pinfunction "PH5(OC4C)_17") (pintype "bidirectional"))
      (node (ref "M3") (pin "1") (pinfunction "1_1") (pintype "passive"))
    )
    (net (code "42") (name "M4") (class "Default")
      (node (ref "FCP") (pin "18") (pinfunction "PH6(OC2B)_18") (pintype "bidirectional"))
      (node (ref "M4") (pin "1") (pinfunction "1_1") (pintype "passive"))
    )
    (net (code "43") (name "MAGREADY") (class "Default")
      (node (ref "U8") (pin "18") (pinfunction "DRDY_M_18") (pintype "bidirectional"))
    )
    (net (code "44") (name "NAV_MISO") (class "Default")
      (node (ref "NAVP") (pin "22") (pinfunction "(MISO/PCINT3)PB3_22") (pintype "bidirectional"))
      (node (ref "NAV_ISCP") (pin "1") (pinfunction "1_1") (pintype "passive"))
    )
    (net (code "45") (name "NAV_MOSI") (class "Default")
      (node (ref "NAVP") (pin "21") (pinfunction "(MOSI/PCINT2)PB2_21") (pintype "bidirectional"))
      (node (ref "NAV_ISCP") (pin "4") (pinfunction "4_4") (pintype "passive"))
    )
    (net (code "46") (name "NAV_SCK") (class "Default")
      (node (ref "NAVP") (pin "20") (pinfunction "(SCK/PCINT1)PB1_20") (pintype "bidirectional"))
      (node (ref "NAV_ISCP") (pin "3") (pinfunction "3_3") (pintype "passive"))
    )
    (net (code "47") (name "Net-(FCP-XTAL1)") (class "Default")
      (node (ref "FCP") (pin "34") (pinfunction "XTAL1_34") (pintype "input"))
      (node (ref "Y1") (pin "3") (pinfunction "3_3") (pintype "passive"))
    )
    (net (code "48") (name "Net-(FCP-XTAL2)") (class "Default")
      (node (ref "FCP") (pin "33") (pinfunction "XTAL2_33") (pintype "output"))
      (node (ref "Y1") (pin "1") (pinfunction "1_1") (pintype "passive"))
    )
    (net (code "49") (name "Net-(IC4-VI)") (class "Default")
      (node (ref "IC4") (pin "3") (pinfunction "VI_3") (pintype "input"))
      (node (ref "JP1") (pin "2") (pinfunction "2_2") (pintype "passive"))
      (node (ref "U$24") (pin "VIN") (pinfunction "VIN_VIN") (pintype "bidirectional"))
      (node (ref "U$25") (pin "VIN") (pinfunction "VIN_VIN") (pintype "bidirectional"))
      (node (ref "U$26") (pin "VIN") (pinfunction "VIN_VIN") (pintype "bidirectional"))
      (node (ref "U$27") (pin "VIN") (pinfunction "VIN_VIN") (pintype "bidirectional"))
    )
    (net (code "50") (name "Net-(IMUP-XTAL1)") (class "Default")
      (node (ref "IMUP") (pin "34") (pinfunction "XTAL1_34") (pintype "input"))
      (node (ref "Y2") (pin "3") (pinfunction "3_3") (pintype "passive"))
    )
    (net (code "51") (name "Net-(IMUP-XTAL2)") (class "Default")
      (node (ref "IMUP") (pin "33") (pinfunction "XTAL2_33") (pintype "output"))
      (node (ref "Y2") (pin "1") (pinfunction "1_1") (pintype "passive"))
    )
    (net (code "52") (name "Net-(NAVP-XTAL1)") (class "Default")
      (node (ref "NAVP") (pin "34") (pinfunction "XTAL1_34") (pintype "input"))
      (node (ref "Y3") (pin "3") (pinfunction "3_3") (pintype "passive"))
    )
    (net (code "53") (name "Net-(NAVP-XTAL2)") (class "Default")
      (node (ref "NAVP") (pin "33") (pinfunction "XTAL2_33") (pintype "output"))
      (node (ref "Y3") (pin "1") (pinfunction "1_1") (pintype "passive"))
    )
    (net (code "54") (name "Net-(Q1-S)") (class "Default")
      (node (ref "Q1") (pin "2") (pinfunction "S_2") (pintype "passive"))
      (node (ref "R4") (pin "1") (pinfunction "1_1") (pintype "passive"))
      (node (ref "U8") (pin "20") (pinfunction "SCL_M_20") (pintype "bidirectional"))
      (node (ref "U8") (pin "24") (pinfunction "SCL_A_24") (pintype "bidirectional"))
    )
    (net (code "55") (name "Net-(Q2-S)") (class "Default")
      (node (ref "Q2") (pin "2") (pinfunction "S_2") (pintype "passive"))
      (node (ref "R5") (pin "1") (pinfunction "1_1") (pintype "passive"))
      (node (ref "U8") (pin "19") (pinfunction "SDA_M_19") (pintype "bidirectional"))
      (node (ref "U8") (pin "25") (pinfunction "SDA_A_25") (pintype "bidirectional"))
    )
    (net (code "56") (name "Net-(Q3-D)") (class "Default")
      (node (ref "Q3") (pin "3") (pinfunction "D_3") (pintype "passive"))
      (node (ref "R3") (pin "1") (pinfunction "1_1") (pintype "passive"))
      (node (ref "U7") (pin "TX") (pinfunction "TX_TX") (pintype "bidirectional"))
    )
    (net (code "57") (name "Net-(Q4-D)") (class "Default")
      (node (ref "Q4") (pin "3") (pinfunction "D_3") (pintype "passive"))
      (node (ref "R7") (pin "1") (pinfunction "1_1") (pintype "passive"))
      (node (ref "U7") (pin "RX") (pinfunction "RX_RX") (pintype "bidirectional"))
    )
    (net (code "58") (name "Net-(U4-PB6(XTAL1{slash}TOSC1))") (class "Default")
      (node (ref "U4") (pin "7") (pinfunction "PB6(XTAL1/TOSC1)_7") (pintype "bidirectional"))
      (node (ref "Y4") (pin "1") (pinfunction "1_1") (pintype "passive"))
    )
    (net (code "59") (name "Net-(U4-PB7(XTAL2{slash}TOSC2))") (class "Default")
      (node (ref "U4") (pin "8") (pinfunction "PB7(XTAL2/TOSC2)_8") (pintype "bidirectional"))
      (node (ref "Y4") (pin "3") (pinfunction "3_3") (pintype "passive"))
    )
    (net (code "60") (name "Net-(U8-C1)") (class "Default")
      (node (ref "C11") (pin "1") (pinfunction "1_1") (pintype "passive"))
      (node (ref "U8") (pin "15") (pinfunction "C1_15") (pintype "bidirectional"))
    )
    (net (code "61") (name "Net-(U8-SET1)") (class "Default")
      (node (ref "C10") (pin "1") (pinfunction "1_1") (pintype "passive"))
      (node (ref "U8") (pin "16") (pinfunction "SET1_16") (pintype "bidirectional"))
    )
    (net (code "62") (name "Net-(U8-SET2)") (class "Default")
      (node (ref "C10") (pin "2") (pinfunction "2_2") (pintype "passive"))
      (node (ref "U8") (pin "12") (pinfunction "SET2_12") (pintype "bidirectional"))
    )
    (net (code "63") (name "RESET") (class "Default")
      (node (ref "FCP") (pin "30") (pinfunction "RESET_30") (pintype "input"))
      (node (ref "FCU_ISCP") (pin "5") (pinfunction "5_5") (pintype "passive"))
      (node (ref "IMUP") (pin "30") (pinfunction "RESET_30") (pintype "input"))
      (node (ref "IMU_ISCP") (pin "5") (pinfunction "5_5") (pintype "passive"))
      (node (ref "NAVP") (pin "30") (pinfunction "RESET_30") (pintype "input"))
      (node (ref "NAV_ISCP") (pin "5") (pinfunction "5_5") (pintype "passive"))
      (node (ref "R6") (pin "1") (pinfunction "1_1") (pintype "passive"))
      (node (ref "S1") (pin "1") (pinfunction "1_1") (pintype "passive"))
      (node (ref "S1") (pin "2") (pinfunction "2_2") (pintype "passive"))
      (node (ref "U4") (pin "29") (pinfunction "PC6(/RESET)_29") (pintype "bidirectional"))
    )
    (net (code "64") (name "RX1") (class "Default")
      (node (ref "IMUP") (pin "45") (pinfunction "(RXD1/INT2)PD2_45") (pintype "bidirectional"))
      (node (ref "Q3") (pin "2") (pinfunction "S_2") (pintype "passive"))
      (node (ref "R8") (pin "1") (pinfunction "1_1") (pintype "passive"))
    )
    (net (code "65") (name "SCL") (class "Default")
      (node (ref "IMUP") (pin "43") (pinfunction "(SCL/INT0)PD0_43") (pintype "bidirectional"))
      (node (ref "Q1") (pin "3") (pinfunction "D_3") (pintype "passive"))
      (node (ref "R2") (pin "1") (pinfunction "1_1") (pintype "passive"))
      (node (ref "U$8") (pin "6") (pinfunction "SCL_6") (pintype "input"))
      (node (ref "U5") (pin "23") (pinfunction "SCL_23") (pintype "bidirectional"))
      (node (ref "U6") (pin "14") (pinfunction "SCL_14") (pintype "bidirectional"))
    )
    (net (code "66") (name "SDA") (class "Default")
      (node (ref "IMUP") (pin "44") (pinfunction "(SDA/INT1)PD1_44") (pintype "bidirectional"))
      (node (ref "Q2") (pin "3") (pinfunction "D_3") (pintype "passive"))
      (node (ref "R1") (pin "1") (pinfunction "1_1") (pintype "passive"))
      (node (ref "U$8") (pin "7") (pinfunction "SDA_7") (pintype "bidirectional"))
      (node (ref "U5") (pin "24") (pinfunction "SDA_24") (pintype "bidirectional"))
      (node (ref "U6") (pin "13") (pinfunction "SDA_13") (pintype "bidirectional"))
    )
    (net (code "67") (name "TX1") (class "Default")
      (node (ref "IMUP") (pin "46") (pinfunction "(TXD1/INT3)PD3_46") (pintype "bidirectional"))
      (node (ref "Q4") (pin "2") (pinfunction "S_2") (pintype "passive"))
      (node (ref "R9") (pin "1") (pinfunction "1_1") (pintype "passive"))
    )
    (net (code "68") (name "unconnected-(FCP-(ADC0)PF0-Pad97)") (class "Default")
      (node (ref "FCP") (pin "97") (pinfunction "(ADC0)PF0_97") (pintype "bidirectional"))
    )
    (net (code "69") (name "unconnected-(FCP-(ADC1)PF1-Pad96)") (class "Default")
      (node (ref "FCP") (pin "96") (pinfunction "(ADC1)PF1_96") (pintype "bidirectional"))
    )
    (net (code "70") (name "unconnected-(FCP-(ADC2)PF2-Pad95)") (class "Default")
      (node (ref "FCP") (pin "95") (pinfunction "(ADC2)PF2_95") (pintype "bidirectional"))
    )
    (net (code "71") (name "unconnected-(FCP-(ADC3)PF3-Pad94)") (class "Default")
      (node (ref "FCP") (pin "94") (pinfunction "(ADC3)PF3_94") (pintype "bidirectional"))
    )
    (net (code "72") (name "unconnected-(FCP-(ADC4{slash}TCK)PF4-Pad93)") (class "Default")
      (node (ref "FCP") (pin "93") (pinfunction "(ADC4/TCK)PF4_93") (pintype "bidirectional"))
    )
    (net (code "73") (name "unconnected-(FCP-(ADC5{slash}TMS)PF5-Pad92)") (class "Default")
      (node (ref "FCP") (pin "92") (pinfunction "(ADC5/TMS)PF5_92") (pintype "bidirectional"))
    )
    (net (code "74") (name "unconnected-(FCP-(ADC6{slash}TDO)PF6-Pad91)") (class "Default")
      (node (ref "FCP") (pin "91") (pinfunction "(ADC6/TDO)PF6_91") (pintype "bidirectional"))
    )
    (net (code "75") (name "unconnected-(FCP-(ADC7{slash}TDI)PF7-Pad90)") (class "Default")
      (node (ref "FCP") (pin "90") (pinfunction "(ADC7/TDI)PF7_90") (pintype "bidirectional"))
    )
    (net (code "76") (name "unconnected-(FCP-(ALE)PG2-Pad70)") (class "Default")
      (node (ref "FCP") (pin "70") (pinfunction "(ALE)PG2_70") (pintype "bidirectional"))
    )
    (net (code "77") (name "unconnected-(FCP-(CLKO{slash}ICP3{slash}INT7)PE7-Pad9)") (class "Default")
      (node (ref "FCP") (pin "9") (pinfunction "(CLKO/ICP3/INT7)PE7_9") (pintype "bidirectional"))
    )
    (net (code "78") (name "unconnected-(FCP-(ICP1)PD4-Pad47)") (class "Default")
      (node (ref "FCP") (pin "47") (pinfunction "(ICP1)PD4_47") (pintype "bidirectional"))
    )
    (net (code "79") (name "unconnected-(FCP-(OC0A{slash}OC1C{slash}PCINT7)PB7-Pad26)") (class "Default")
      (node (ref "FCP") (pin "26") (pinfunction "(OC0A/OC1C/PCINT7)PB7_26") (pintype "bidirectional"))
    )
    (net (code "80") (name "unconnected-(FCP-(OC0B)PG5-Pad1)") (class "Default")
      (node (ref "FCP") (pin "1") (pinfunction "(OC0B)PG5_1") (pintype "bidirectional"))
    )
    (net (code "81") (name "unconnected-(FCP-(OC1A{slash}PCINT5)PB5-Pad24)") (class "Default")
      (node (ref "FCP") (pin "24") (pinfunction "(OC1A/PCINT5)PB5_24") (pintype "bidirectional"))
    )
    (net (code "82") (name "unconnected-(FCP-(OC1B{slash}PCINT6)PB6-Pad25)") (class "Default")
      (node (ref "FCP") (pin "25") (pinfunction "(OC1B/PCINT6)PB6_25") (pintype "bidirectional"))
    )
    (net (code "83") (name "unconnected-(FCP-(OC2A{slash}PCINT4)PB4-Pad23)") (class "Default")
      (node (ref "FCP") (pin "23") (pinfunction "(OC2A/PCINT4)PB4_23") (pintype "bidirectional"))
    )
    (net (code "84") (name "unconnected-(FCP-(OC3A{slash}AIN1)PE3-Pad5)") (class "Default")
      (node (ref "FCP") (pin "5") (pinfunction "(OC3A/AIN1)PE3_5") (pintype "bidirectional"))
    )
    (net (code "85") (name "unconnected-(FCP-(OC3B{slash}INT4)PE4-Pad6)") (class "Default")
      (node (ref "FCP") (pin "6") (pinfunction "(OC3B/INT4)PE4_6") (pintype "bidirectional"))
    )
    (net (code "86") (name "unconnected-(FCP-(OC3C{slash}INT5)PE5-Pad7)") (class "Default")
      (node (ref "FCP") (pin "7") (pinfunction "(OC3C/INT5)PE5_7") (pintype "bidirectional"))
    )
    (net (code "87") (name "unconnected-(FCP-(RD)PG1-Pad52)") (class "Default")
      (node (ref "FCP") (pin "52") (pinfunction "(RD)PG1_52") (pintype "bidirectional"))
    )
    (net (code "88") (name "unconnected-(FCP-(RXD0{slash}PCIN8)PE0-Pad2)") (class "Default")
      (node (ref "FCP") (pin "2") (pinfunction "(RXD0/PCIN8)PE0_2") (pintype "bidirectional"))
    )
    (net (code "89") (name "unconnected-(FCP-(RXD1{slash}INT2)PD2-Pad45)") (class "Default")
      (node (ref "FCP") (pin "45") (pinfunction "(RXD1/INT2)PD2_45") (pintype "bidirectional"))
    )
    (net (code "90") (name "unconnected-(FCP-(SCL{slash}INT0)PD0-Pad43)") (class "Default")
      (node (ref "FCP") (pin "43") (pinfunction "(SCL/INT0)PD0_43") (pintype "bidirectional"))
    )
    (net (code "91") (name "unconnected-(FCP-(SDA{slash}INT1)PD1-Pad44)") (class "Default")
      (node (ref "FCP") (pin "44") (pinfunction "(SDA/INT1)PD1_44") (pintype "bidirectional"))
    )
    (net (code "92") (name "unconnected-(FCP-(SS{slash}PCINT0)PB0-Pad19)") (class "Default")
      (node (ref "FCP") (pin "19") (pinfunction "(SS/PCINT0)PB0_19") (pintype "bidirectional"))
    )
    (net (code "93") (name "unconnected-(FCP-(T0)PD7-Pad50)") (class "Default")
      (node (ref "FCP") (pin "50") (pinfunction "(T0)PD7_50") (pintype "bidirectional"))
    )
    (net (code "94") (name "unconnected-(FCP-(T1)PD6-Pad49)") (class "Default")
      (node (ref "FCP") (pin "49") (pinfunction "(T1)PD6_49") (pintype "bidirectional"))
    )
    (net (code "95") (name "unconnected-(FCP-(T3{slash}INT6)PE6-Pad8)") (class "Default")
      (node (ref "FCP") (pin "8") (pinfunction "(T3/INT6)PE6_8") (pintype "bidirectional"))
    )
    (net (code "96") (name "unconnected-(FCP-(TOSC1)PG4-Pad29)") (class "Default")
      (node (ref "FCP") (pin "29") (pinfunction "(TOSC1)PG4_29") (pintype "bidirectional"))
    )
    (net (code "97") (name "unconnected-(FCP-(TOSC2)PG3-Pad28)") (class "Default")
      (node (ref "FCP") (pin "28") (pinfunction "(TOSC2)PG3_28") (pintype "bidirectional"))
    )
    (net (code "98") (name "unconnected-(FCP-(TXD0)PE1-Pad3)") (class "Default")
      (node (ref "FCP") (pin "3") (pinfunction "(TXD0)PE1_3") (pintype "bidirectional"))
    )
    (net (code "99") (name "unconnected-(FCP-(TXD1{slash}INT3)PD3-Pad46)") (class "Default")
      (node (ref "FCP") (pin "46") (pinfunction "(TXD1/INT3)PD3_46") (pintype "bidirectional"))
    )
    (net (code "100") (name "unconnected-(FCP-(WR)PG0-Pad51)") (class "Default")
      (node (ref "FCP") (pin "51") (pinfunction "(WR)PG0_51") (pintype "bidirectional"))
    )
    (net (code "101") (name "unconnected-(FCP-(XCK0{slash}AIN0)PE2-Pad4)") (class "Default")
      (node (ref "FCP") (pin "4") (pinfunction "(XCK0/AIN0)PE2_4") (pintype "bidirectional"))
    )
    (net (code "102") (name "unconnected-(FCP-(XCK1)PD5-Pad48)") (class "Default")
      (node (ref "FCP") (pin "48") (pinfunction "(XCK1)PD5_48") (pintype "bidirectional"))
    )
    (net (code "103") (name "unconnected-(FCP-PH0(RXD2)-Pad12)") (class "Default")
      (node (ref "FCP") (pin "12") (pinfunction "PH0(RXD2)_12") (pintype "bidirectional"))
    )
    (net (code "104") (name "unconnected-(FCP-PH1(TXD2)-Pad13)") (class "Default")
      (node (ref "FCP") (pin "13") (pinfunction "PH1(TXD2)_13") (pintype "bidirectional"))
    )
    (net (code "105") (name "unconnected-(FCP-PH2(XCK2)-Pad14)") (class "Default")
      (node (ref "FCP") (pin "14") (pinfunction "PH2(XCK2)_14") (pintype "bidirectional"))
    )
    (net (code "106") (name "unconnected-(FCP-PH7(T4)-Pad27)") (class "Default")
      (node (ref "FCP") (pin "27") (pinfunction "PH7(T4)_27") (pintype "bidirectional"))
    )
    (net (code "107") (name "unconnected-(FCP-PJ0(RXD3{slash}PCINT9)-Pad63)") (class "Default")
      (node (ref "FCP") (pin "63") (pinfunction "PJ0(RXD3/PCINT9)_63") (pintype "bidirectional"))
    )
    (net (code "108") (name "unconnected-(FCP-PJ1(TXD3{slash}PCINT10)-Pad64)") (class "Default")
      (node (ref "FCP") (pin "64") (pinfunction "PJ1(TXD3/PCINT10)_64") (pintype "bidirectional"))
    )
    (net (code "109") (name "unconnected-(FCP-PK0(ADC8{slash}PCINT16)-Pad89)") (class "Default")
      (node (ref "FCP") (pin "89") (pinfunction "PK0(ADC8/PCINT16)_89") (pintype "bidirectional"))
    )
    (net (code "110") (name "unconnected-(FCP-PK1(ADC9{slash}PCINT17)-Pad88)") (class "Default")
      (node (ref "FCP") (pin "88") (pinfunction "PK1(ADC9/PCINT17)_88") (pintype "bidirectional"))
    )
    (net (code "111") (name "unconnected-(FCP-PK2(ADC10{slash}PCINT18)-Pad87)") (class "Default")
      (node (ref "FCP") (pin "87") (pinfunction "PK2(ADC10/PCINT18)_87") (pintype "bidirectional"))
    )
    (net (code "112") (name "unconnected-(FCP-PK3(ADC11{slash}PCINT19)-Pad86)") (class "Default")
      (node (ref "FCP") (pin "86") (pinfunction "PK3(ADC11/PCINT19)_86") (pintype "bidirectional"))
    )
    (net (code "113") (name "unconnected-(FCP-PK4(ADC12{slash}PCINT20)-Pad85)") (class "Default")
      (node (ref "FCP") (pin "85") (pinfunction "PK4(ADC12/PCINT20)_85") (pintype "bidirectional"))
    )
    (net (code "114") (name "unconnected-(FCP-PK5(ADC13{slash}PCINT21)-Pad84)") (class "Default")
      (node (ref "FCP") (pin "84") (pinfunction "PK5(ADC13/PCINT21)_84") (pintype "bidirectional"))
    )
    (net (code "115") (name "unconnected-(FCP-PK6(ADC14{slash}PCINT22)-Pad83)") (class "Default")
      (node (ref "FCP") (pin "83") (pinfunction "PK6(ADC14/PCINT22)_83") (pintype "bidirectional"))
    )
    (net (code "116") (name "unconnected-(FCP-PK7(ADC15{slash}PCINT23)-Pad82)") (class "Default")
      (node (ref "FCP") (pin "82") (pinfunction "PK7(ADC15/PCINT23)_82") (pintype "bidirectional"))
    )
    (net (code "117") (name "unconnected-(FCP-PL0(ICP4)-Pad35)") (class "Default")
      (node (ref "FCP") (pin "35") (pinfunction "PL0(ICP4)_35") (pintype "bidirectional"))
    )
    (net (code "118") (name "unconnected-(FCP-PL1(ICP5)-Pad36)") (class "Default")
      (node (ref "FCP") (pin "36") (pinfunction "PL1(ICP5)_36") (pintype "bidirectional"))
    )
    (net (code "119") (name "unconnected-(FCP-PL2(T5)-Pad37)") (class "Default")
      (node (ref "FCP") (pin "37") (pinfunction "PL2(T5)_37") (pintype "bidirectional"))
    )
    (net (code "120") (name "unconnected-(FCP-PL3(OC5A)-Pad38)") (class "Default")
      (node (ref "FCP") (pin "38") (pinfunction "PL3(OC5A)_38") (pintype "bidirectional"))
    )
    (net (code "121") (name "unconnected-(FCP-PL4(OC5B)-Pad39)") (class "Default")
      (node (ref "FCP") (pin "39") (pinfunction "PL4(OC5B)_39") (pintype "bidirectional"))
    )
    (net (code "122") (name "unconnected-(FCP-PL5(OC5C)-Pad40)") (class "Default")
      (node (ref "FCP") (pin "40") (pinfunction "PL5(OC5C)_40") (pintype "bidirectional"))
    )
    (net (code "123") (name "unconnected-(FCP-PL6-Pad41)") (class "Default")
      (node (ref "FCP") (pin "41") (pinfunction "PL6_41") (pintype "bidirectional"))
    )
    (net (code "124") (name "unconnected-(FCP-PL7-Pad42)") (class "Default")
      (node (ref "FCP") (pin "42") (pinfunction "PL7_42") (pintype "bidirectional"))
    )
    (net (code "125") (name "unconnected-(IMUP-(ADC0)PF0-Pad97)") (class "Default")
      (node (ref "IMUP") (pin "97") (pinfunction "(ADC0)PF0_97") (pintype "bidirectional"))
    )
    (net (code "126") (name "unconnected-(IMUP-(ADC1)PF1-Pad96)") (class "Default")
      (node (ref "IMUP") (pin "96") (pinfunction "(ADC1)PF1_96") (pintype "bidirectional"))
    )
    (net (code "127") (name "unconnected-(IMUP-(ADC2)PF2-Pad95)") (class "Default")
      (node (ref "IMUP") (pin "95") (pinfunction "(ADC2)PF2_95") (pintype "bidirectional"))
    )
    (net (code "128") (name "unconnected-(IMUP-(ADC3)PF3-Pad94)") (class "Default")
      (node (ref "IMUP") (pin "94") (pinfunction "(ADC3)PF3_94") (pintype "bidirectional"))
    )
    (net (code "129") (name "unconnected-(IMUP-(ADC4{slash}TCK)PF4-Pad93)") (class "Default")
      (node (ref "IMUP") (pin "93") (pinfunction "(ADC4/TCK)PF4_93") (pintype "bidirectional"))
    )
    (net (code "130") (name "unconnected-(IMUP-(ADC5{slash}TMS)PF5-Pad92)") (class "Default")
      (node (ref "IMUP") (pin "92") (pinfunction "(ADC5/TMS)PF5_92") (pintype "bidirectional"))
    )
    (net (code "131") (name "unconnected-(IMUP-(ADC6{slash}TDO)PF6-Pad91)") (class "Default")
      (node (ref "IMUP") (pin "91") (pinfunction "(ADC6/TDO)PF6_91") (pintype "bidirectional"))
    )
    (net (code "132") (name "unconnected-(IMUP-(ADC7{slash}TDI)PF7-Pad90)") (class "Default")
      (node (ref "IMUP") (pin "90") (pinfunction "(ADC7/TDI)PF7_90") (pintype "bidirectional"))
    )
    (net (code "133") (name "unconnected-(IMUP-(ALE)PG2-Pad70)") (class "Default")
      (node (ref "IMUP") (pin "70") (pinfunction "(ALE)PG2_70") (pintype "bidirectional"))
    )
    (net (code "134") (name "unconnected-(IMUP-(CLKO{slash}ICP3{slash}INT7)PE7-Pad9)") (class "Default")
      (node (ref "IMUP") (pin "9") (pinfunction "(CLKO/ICP3/INT7)PE7_9") (pintype "bidirectional"))
    )
    (net (code "135") (name "unconnected-(IMUP-(ICP1)PD4-Pad47)") (class "Default")
      (node (ref "IMUP") (pin "47") (pinfunction "(ICP1)PD4_47") (pintype "bidirectional"))
    )
    (net (code "136") (name "unconnected-(IMUP-(OC0A{slash}OC1C{slash}PCINT7)PB7-Pad26)") (class "Default")
      (node (ref "IMUP") (pin "26") (pinfunction "(OC0A/OC1C/PCINT7)PB7_26") (pintype "bidirectional"))
    )
    (net (code "137") (name "unconnected-(IMUP-(OC0B)PG5-Pad1)") (class "Default")
      (node (ref "IMUP") (pin "1") (pinfunction "(OC0B)PG5_1") (pintype "bidirectional"))
    )
    (net (code "138") (name "unconnected-(IMUP-(OC1A{slash}PCINT5)PB5-Pad24)") (class "Default")
      (node (ref "IMUP") (pin "24") (pinfunction "(OC1A/PCINT5)PB5_24") (pintype "bidirectional"))
    )
    (net (code "139") (name "unconnected-(IMUP-(OC1B{slash}PCINT6)PB6-Pad25)") (class "Default")
      (node (ref "IMUP") (pin "25") (pinfunction "(OC1B/PCINT6)PB6_25") (pintype "bidirectional"))
    )
    (net (code "140") (name "unconnected-(IMUP-(OC2A{slash}PCINT4)PB4-Pad23)") (class "Default")
      (node (ref "IMUP") (pin "23") (pinfunction "(OC2A/PCINT4)PB4_23") (pintype "bidirectional"))
    )
    (net (code "141") (name "unconnected-(IMUP-(OC3A{slash}AIN1)PE3-Pad5)") (class "Default")
      (node (ref "IMUP") (pin "5") (pinfunction "(OC3A/AIN1)PE3_5") (pintype "bidirectional"))
    )
    (net (code "142") (name "unconnected-(IMUP-(OC3B{slash}INT4)PE4-Pad6)") (class "Default")
      (node (ref "IMUP") (pin "6") (pinfunction "(OC3B/INT4)PE4_6") (pintype "bidirectional"))
    )
    (net (code "143") (name "unconnected-(IMUP-(OC3C{slash}INT5)PE5-Pad7)") (class "Default")
      (node (ref "IMUP") (pin "7") (pinfunction "(OC3C/INT5)PE5_7") (pintype "bidirectional"))
    )
    (net (code "144") (name "unconnected-(IMUP-(RD)PG1-Pad52)") (class "Default")
      (node (ref "IMUP") (pin "52") (pinfunction "(RD)PG1_52") (pintype "bidirectional"))
    )
    (net (code "145") (name "unconnected-(IMUP-(RXD0{slash}PCIN8)PE0-Pad2)") (class "Default")
      (node (ref "IMUP") (pin "2") (pinfunction "(RXD0/PCIN8)PE0_2") (pintype "bidirectional"))
    )
    (net (code "146") (name "unconnected-(IMUP-(SS{slash}PCINT0)PB0-Pad19)") (class "Default")
      (node (ref "IMUP") (pin "19") (pinfunction "(SS/PCINT0)PB0_19") (pintype "bidirectional"))
    )
    (net (code "147") (name "unconnected-(IMUP-(T0)PD7-Pad50)") (class "Default")
      (node (ref "IMUP") (pin "50") (pinfunction "(T0)PD7_50") (pintype "bidirectional"))
    )
    (net (code "148") (name "unconnected-(IMUP-(T1)PD6-Pad49)") (class "Default")
      (node (ref "IMUP") (pin "49") (pinfunction "(T1)PD6_49") (pintype "bidirectional"))
    )
    (net (code "149") (name "unconnected-(IMUP-(T3{slash}INT6)PE6-Pad8)") (class "Default")
      (node (ref "IMUP") (pin "8") (pinfunction "(T3/INT6)PE6_8") (pintype "bidirectional"))
    )
    (net (code "150") (name "unconnected-(IMUP-(TOSC1)PG4-Pad29)") (class "Default")
      (node (ref "IMUP") (pin "29") (pinfunction "(TOSC1)PG4_29") (pintype "bidirectional"))
    )
    (net (code "151") (name "unconnected-(IMUP-(TOSC2)PG3-Pad28)") (class "Default")
      (node (ref "IMUP") (pin "28") (pinfunction "(TOSC2)PG3_28") (pintype "bidirectional"))
    )
    (net (code "152") (name "unconnected-(IMUP-(TXD0)PE1-Pad3)") (class "Default")
      (node (ref "IMUP") (pin "3") (pinfunction "(TXD0)PE1_3") (pintype "bidirectional"))
    )
    (net (code "153") (name "unconnected-(IMUP-(WR)PG0-Pad51)") (class "Default")
      (node (ref "IMUP") (pin "51") (pinfunction "(WR)PG0_51") (pintype "bidirectional"))
    )
    (net (code "154") (name "unconnected-(IMUP-(XCK0{slash}AIN0)PE2-Pad4)") (class "Default")
      (node (ref "IMUP") (pin "4") (pinfunction "(XCK0/AIN0)PE2_4") (pintype "bidirectional"))
    )
    (net (code "155") (name "unconnected-(IMUP-(XCK1)PD5-Pad48)") (class "Default")
      (node (ref "IMUP") (pin "48") (pinfunction "(XCK1)PD5_48") (pintype "bidirectional"))
    )
    (net (code "156") (name "unconnected-(IMUP-PH0(RXD2)-Pad12)") (class "Default")
      (node (ref "IMUP") (pin "12") (pinfunction "PH0(RXD2)_12") (pintype "bidirectional"))
    )
    (net (code "157") (name "unconnected-(IMUP-PH1(TXD2)-Pad13)") (class "Default")
      (node (ref "IMUP") (pin "13") (pinfunction "PH1(TXD2)_13") (pintype "bidirectional"))
    )
    (net (code "158") (name "unconnected-(IMUP-PH2(XCK2)-Pad14)") (class "Default")
      (node (ref "IMUP") (pin "14") (pinfunction "PH2(XCK2)_14") (pintype "bidirectional"))
    )
    (net (code "159") (name "unconnected-(IMUP-PH3(OC4A)-Pad15)") (class "Default")
      (node (ref "IMUP") (pin "15") (pinfunction "PH3(OC4A)_15") (pintype "bidirectional"))
    )
    (net (code "160") (name "unconnected-(IMUP-PH4(OC4B)-Pad16)") (class "Default")
      (node (ref "IMUP") (pin "16") (pinfunction "PH4(OC4B)_16") (pintype "bidirectional"))
    )
    (net (code "161") (name "unconnected-(IMUP-PH5(OC4C)-Pad17)") (class "Default")
      (node (ref "IMUP") (pin "17") (pinfunction "PH5(OC4C)_17") (pintype "bidirectional"))
    )
    (net (code "162") (name "unconnected-(IMUP-PH6(OC2B)-Pad18)") (class "Default")
      (node (ref "IMUP") (pin "18") (pinfunction "PH6(OC2B)_18") (pintype "bidirectional"))
    )
    (net (code "163") (name "unconnected-(IMUP-PH7(T4)-Pad27)") (class "Default")
      (node (ref "IMUP") (pin "27") (pinfunction "PH7(T4)_27") (pintype "bidirectional"))
    )
    (net (code "164") (name "unconnected-(IMUP-PJ0(RXD3{slash}PCINT9)-Pad63)") (class "Default")
      (node (ref "IMUP") (pin "63") (pinfunction "PJ0(RXD3/PCINT9)_63") (pintype "bidirectional"))
    )
    (net (code "165") (name "unconnected-(IMUP-PJ1(TXD3{slash}PCINT10)-Pad64)") (class "Default")
      (node (ref "IMUP") (pin "64") (pinfunction "PJ1(TXD3/PCINT10)_64") (pintype "bidirectional"))
    )
    (net (code "166") (name "unconnected-(IMUP-PK0(ADC8{slash}PCINT16)-Pad89)") (class "Default")
      (node (ref "IMUP") (pin "89") (pinfunction "PK0(ADC8/PCINT16)_89") (pintype "bidirectional"))
    )
    (net (code "167") (name "unconnected-(IMUP-PK1(ADC9{slash}PCINT17)-Pad88)") (class "Default")
      (node (ref "IMUP") (pin "88") (pinfunction "PK1(ADC9/PCINT17)_88") (pintype "bidirectional"))
    )
    (net (code "168") (name "unconnected-(IMUP-PK2(ADC10{slash}PCINT18)-Pad87)") (class "Default")
      (node (ref "IMUP") (pin "87") (pinfunction "PK2(ADC10/PCINT18)_87") (pintype "bidirectional"))
    )
    (net (code "169") (name "unconnected-(IMUP-PK3(ADC11{slash}PCINT19)-Pad86)") (class "Default")
      (node (ref "IMUP") (pin "86") (pinfunction "PK3(ADC11/PCINT19)_86") (pintype "bidirectional"))
    )
    (net (code "170") (name "unconnected-(IMUP-PK4(ADC12{slash}PCINT20)-Pad85)") (class "Default")
      (node (ref "IMUP") (pin "85") (pinfunction "PK4(ADC12/PCINT20)_85") (pintype "bidirectional"))
    )
    (net (code "171") (name "unconnected-(IMUP-PK5(ADC13{slash}PCINT21)-Pad84)") (class "Default")
      (node (ref "IMUP") (pin "84") (pinfunction "PK5(ADC13/PCINT21)_84") (pintype "bidirectional"))
    )
    (net (code "172") (name "unconnected-(IMUP-PK6(ADC14{slash}PCINT22)-Pad83)") (class "Default")
      (node (ref "IMUP") (pin "83") (pinfunction "PK6(ADC14/PCINT22)_83") (pintype "bidirectional"))
    )
    (net (code "173") (name "unconnected-(IMUP-PK7(ADC15{slash}PCINT23)-Pad82)") (class "Default")
      (node (ref "IMUP") (pin "82") (pinfunction "PK7(ADC15/PCINT23)_82") (pintype "bidirectional"))
    )
    (net (code "174") (name "unconnected-(IMUP-PL0(ICP4)-Pad35)") (class "Default")
      (node (ref "IMUP") (pin "35") (pinfunction "PL0(ICP4)_35") (pintype "bidirectional"))
    )
    (net (code "175") (name "unconnected-(IMUP-PL1(ICP5)-Pad36)") (class "Default")
      (node (ref "IMUP") (pin "36") (pinfunction "PL1(ICP5)_36") (pintype "bidirectional"))
    )
    (net (code "176") (name "unconnected-(IMUP-PL2(T5)-Pad37)") (class "Default")
      (node (ref "IMUP") (pin "37") (pinfunction "PL2(T5)_37") (pintype "bidirectional"))
    )
    (net (code "177") (name "unconnected-(IMUP-PL3(OC5A)-Pad38)") (class "Default")
      (node (ref "IMUP") (pin "38") (pinfunction "PL3(OC5A)_38") (pintype "bidirectional"))
    )
    (net (code "178") (name "unconnected-(IMUP-PL4(OC5B)-Pad39)") (class "Default")
      (node (ref "IMUP") (pin "39") (pinfunction "PL4(OC5B)_39") (pintype "bidirectional"))
    )
    (net (code "179") (name "unconnected-(IMUP-PL5(OC5C)-Pad40)") (class "Default")
      (node (ref "IMUP") (pin "40") (pinfunction "PL5(OC5C)_40") (pintype "bidirectional"))
    )
    (net (code "180") (name "unconnected-(IMUP-PL6-Pad41)") (class "Default")
      (node (ref "IMUP") (pin "41") (pinfunction "PL6_41") (pintype "bidirectional"))
    )
    (net (code "181") (name "unconnected-(IMUP-PL7-Pad42)") (class "Default")
      (node (ref "IMUP") (pin "42") (pinfunction "PL7_42") (pintype "bidirectional"))
    )
    (net (code "182") (name "unconnected-(NAVP-(ADC0)PF0-Pad97)") (class "Default")
      (node (ref "NAVP") (pin "97") (pinfunction "(ADC0)PF0_97") (pintype "bidirectional"))
    )
    (net (code "183") (name "unconnected-(NAVP-(ADC1)PF1-Pad96)") (class "Default")
      (node (ref "NAVP") (pin "96") (pinfunction "(ADC1)PF1_96") (pintype "bidirectional"))
    )
    (net (code "184") (name "unconnected-(NAVP-(ADC2)PF2-Pad95)") (class "Default")
      (node (ref "NAVP") (pin "95") (pinfunction "(ADC2)PF2_95") (pintype "bidirectional"))
    )
    (net (code "185") (name "unconnected-(NAVP-(ADC3)PF3-Pad94)") (class "Default")
      (node (ref "NAVP") (pin "94") (pinfunction "(ADC3)PF3_94") (pintype "bidirectional"))
    )
    (net (code "186") (name "unconnected-(NAVP-(ADC4{slash}TCK)PF4-Pad93)") (class "Default")
      (node (ref "NAVP") (pin "93") (pinfunction "(ADC4/TCK)PF4_93") (pintype "bidirectional"))
    )
    (net (code "187") (name "unconnected-(NAVP-(ADC5{slash}TMS)PF5-Pad92)") (class "Default")
      (node (ref "NAVP") (pin "92") (pinfunction "(ADC5/TMS)PF5_92") (pintype "bidirectional"))
    )
    (net (code "188") (name "unconnected-(NAVP-(ADC6{slash}TDO)PF6-Pad91)") (class "Default")
      (node (ref "NAVP") (pin "91") (pinfunction "(ADC6/TDO)PF6_91") (pintype "bidirectional"))
    )
    (net (code "189") (name "unconnected-(NAVP-(ADC7{slash}TDI)PF7-Pad90)") (class "Default")
      (node (ref "NAVP") (pin "90") (pinfunction "(ADC7/TDI)PF7_90") (pintype "bidirectional"))
    )
    (net (code "190") (name "unconnected-(NAVP-(ALE)PG2-Pad70)") (class "Default")
      (node (ref "NAVP") (pin "70") (pinfunction "(ALE)PG2_70") (pintype "bidirectional"))
    )
    (net (code "191") (name "unconnected-(NAVP-(CLKO{slash}ICP3{slash}INT7)PE7-Pad9)") (class "Default")
      (node (ref "NAVP") (pin "9") (pinfunction "(CLKO/ICP3/INT7)PE7_9") (pintype "bidirectional"))
    )
    (net (code "192") (name "unconnected-(NAVP-(ICP1)PD4-Pad47)") (class "Default")
      (node (ref "NAVP") (pin "47") (pinfunction "(ICP1)PD4_47") (pintype "bidirectional"))
    )
    (net (code "193") (name "unconnected-(NAVP-(OC0A{slash}OC1C{slash}PCINT7)PB7-Pad26)") (class "Default")
      (node (ref "NAVP") (pin "26") (pinfunction "(OC0A/OC1C/PCINT7)PB7_26") (pintype "bidirectional"))
    )
    (net (code "194") (name "unconnected-(NAVP-(OC0B)PG5-Pad1)") (class "Default")
      (node (ref "NAVP") (pin "1") (pinfunction "(OC0B)PG5_1") (pintype "bidirectional"))
    )
    (net (code "195") (name "unconnected-(NAVP-(OC1A{slash}PCINT5)PB5-Pad24)") (class "Default")
      (node (ref "NAVP") (pin "24") (pinfunction "(OC1A/PCINT5)PB5_24") (pintype "bidirectional"))
    )
    (net (code "196") (name "unconnected-(NAVP-(OC1B{slash}PCINT6)PB6-Pad25)") (class "Default")
      (node (ref "NAVP") (pin "25") (pinfunction "(OC1B/PCINT6)PB6_25") (pintype "bidirectional"))
    )
    (net (code "197") (name "unconnected-(NAVP-(OC2A{slash}PCINT4)PB4-Pad23)") (class "Default")
      (node (ref "NAVP") (pin "23") (pinfunction "(OC2A/PCINT4)PB4_23") (pintype "bidirectional"))
    )
    (net (code "198") (name "unconnected-(NAVP-(OC3A{slash}AIN1)PE3-Pad5)") (class "Default")
      (node (ref "NAVP") (pin "5") (pinfunction "(OC3A/AIN1)PE3_5") (pintype "bidirectional"))
    )
    (net (code "199") (name "unconnected-(NAVP-(OC3B{slash}INT4)PE4-Pad6)") (class "Default")
      (node (ref "NAVP") (pin "6") (pinfunction "(OC3B/INT4)PE4_6") (pintype "bidirectional"))
    )
    (net (code "200") (name "unconnected-(NAVP-(OC3C{slash}INT5)PE5-Pad7)") (class "Default")
      (node (ref "NAVP") (pin "7") (pinfunction "(OC3C/INT5)PE5_7") (pintype "bidirectional"))
    )
    (net (code "201") (name "unconnected-(NAVP-(RD)PG1-Pad52)") (class "Default")
      (node (ref "NAVP") (pin "52") (pinfunction "(RD)PG1_52") (pintype "bidirectional"))
    )
    (net (code "202") (name "unconnected-(NAVP-(RXD0{slash}PCIN8)PE0-Pad2)") (class "Default")
      (node (ref "NAVP") (pin "2") (pinfunction "(RXD0/PCIN8)PE0_2") (pintype "bidirectional"))
    )
    (net (code "203") (name "unconnected-(NAVP-(RXD1{slash}INT2)PD2-Pad45)") (class "Default")
      (node (ref "NAVP") (pin "45") (pinfunction "(RXD1/INT2)PD2_45") (pintype "bidirectional"))
    )
    (net (code "204") (name "unconnected-(NAVP-(SCL{slash}INT0)PD0-Pad43)") (class "Default")
      (node (ref "NAVP") (pin "43") (pinfunction "(SCL/INT0)PD0_43") (pintype "bidirectional"))
    )
    (net (code "205") (name "unconnected-(NAVP-(SDA{slash}INT1)PD1-Pad44)") (class "Default")
      (node (ref "NAVP") (pin "44") (pinfunction "(SDA/INT1)PD1_44") (pintype "bidirectional"))
    )
    (net (code "206") (name "unconnected-(NAVP-(SS{slash}PCINT0)PB0-Pad19)") (class "Default")
      (node (ref "NAVP") (pin "19") (pinfunction "(SS/PCINT0)PB0_19") (pintype "bidirectional"))
    )
    (net (code "207") (name "unconnected-(NAVP-(T0)PD7-Pad50)") (class "Default")
      (node (ref "NAVP") (pin "50") (pinfunction "(T0)PD7_50") (pintype "bidirectional"))
    )
    (net (code "208") (name "unconnected-(NAVP-(T1)PD6-Pad49)") (class "Default")
      (node (ref "NAVP") (pin "49") (pinfunction "(T1)PD6_49") (pintype "bidirectional"))
    )
    (net (code "209") (name "unconnected-(NAVP-(T3{slash}INT6)PE6-Pad8)") (class "Default")
      (node (ref "NAVP") (pin "8") (pinfunction "(T3/INT6)PE6_8") (pintype "bidirectional"))
    )
    (net (code "210") (name "unconnected-(NAVP-(TOSC1)PG4-Pad29)") (class "Default")
      (node (ref "NAVP") (pin "29") (pinfunction "(TOSC1)PG4_29") (pintype "bidirectional"))
    )
    (net (code "211") (name "unconnected-(NAVP-(TOSC2)PG3-Pad28)") (class "Default")
      (node (ref "NAVP") (pin "28") (pinfunction "(TOSC2)PG3_28") (pintype "bidirectional"))
    )
    (net (code "212") (name "unconnected-(NAVP-(TXD0)PE1-Pad3)") (class "Default")
      (node (ref "NAVP") (pin "3") (pinfunction "(TXD0)PE1_3") (pintype "bidirectional"))
    )
    (net (code "213") (name "unconnected-(NAVP-(TXD1{slash}INT3)PD3-Pad46)") (class "Default")
      (node (ref "NAVP") (pin "46") (pinfunction "(TXD1/INT3)PD3_46") (pintype "bidirectional"))
    )
    (net (code "214") (name "unconnected-(NAVP-(WR)PG0-Pad51)") (class "Default")
      (node (ref "NAVP") (pin "51") (pinfunction "(WR)PG0_51") (pintype "bidirectional"))
    )
    (net (code "215") (name "unconnected-(NAVP-(XCK0{slash}AIN0)PE2-Pad4)") (class "Default")
      (node (ref "NAVP") (pin "4") (pinfunction "(XCK0/AIN0)PE2_4") (pintype "bidirectional"))
    )
    (net (code "216") (name "unconnected-(NAVP-(XCK1)PD5-Pad48)") (class "Default")
      (node (ref "NAVP") (pin "48") (pinfunction "(XCK1)PD5_48") (pintype "bidirectional"))
    )
    (net (code "217") (name "unconnected-(NAVP-PH0(RXD2)-Pad12)") (class "Default")
      (node (ref "NAVP") (pin "12") (pinfunction "PH0(RXD2)_12") (pintype "bidirectional"))
    )
    (net (code "218") (name "unconnected-(NAVP-PH1(TXD2)-Pad13)") (class "Default")
      (node (ref "NAVP") (pin "13") (pinfunction "PH1(TXD2)_13") (pintype "bidirectional"))
    )
    (net (code "219") (name "unconnected-(NAVP-PH2(XCK2)-Pad14)") (class "Default")
      (node (ref "NAVP") (pin "14") (pinfunction "PH2(XCK2)_14") (pintype "bidirectional"))
    )
    (net (code "220") (name "unconnected-(NAVP-PH3(OC4A)-Pad15)") (class "Default")
      (node (ref "NAVP") (pin "15") (pinfunction "PH3(OC4A)_15") (pintype "bidirectional"))
    )
    (net (code "221") (name "unconnected-(NAVP-PH4(OC4B)-Pad16)") (class "Default")
      (node (ref "NAVP") (pin "16") (pinfunction "PH4(OC4B)_16") (pintype "bidirectional"))
    )
    (net (code "222") (name "unconnected-(NAVP-PH5(OC4C)-Pad17)") (class "Default")
      (node (ref "NAVP") (pin "17") (pinfunction "PH5(OC4C)_17") (pintype "bidirectional"))
    )
    (net (code "223") (name "unconnected-(NAVP-PH6(OC2B)-Pad18)") (class "Default")
      (node (ref "NAVP") (pin "18") (pinfunction "PH6(OC2B)_18") (pintype "bidirectional"))
    )
    (net (code "224") (name "unconnected-(NAVP-PH7(T4)-Pad27)") (class "Default")
      (node (ref "NAVP") (pin "27") (pinfunction "PH7(T4)_27") (pintype "bidirectional"))
    )
    (net (code "225") (name "unconnected-(NAVP-PJ0(RXD3{slash}PCINT9)-Pad63)") (class "Default")
      (node (ref "NAVP") (pin "63") (pinfunction "PJ0(RXD3/PCINT9)_63") (pintype "bidirectional"))
    )
    (net (code "226") (name "unconnected-(NAVP-PJ1(TXD3{slash}PCINT10)-Pad64)") (class "Default")
      (node (ref "NAVP") (pin "64") (pinfunction "PJ1(TXD3/PCINT10)_64") (pintype "bidirectional"))
    )
    (net (code "227") (name "unconnected-(NAVP-PK0(ADC8{slash}PCINT16)-Pad89)") (class "Default")
      (node (ref "NAVP") (pin "89") (pinfunction "PK0(ADC8/PCINT16)_89") (pintype "bidirectional"))
    )
    (net (code "228") (name "unconnected-(NAVP-PK1(ADC9{slash}PCINT17)-Pad88)") (class "Default")
      (node (ref "NAVP") (pin "88") (pinfunction "PK1(ADC9/PCINT17)_88") (pintype "bidirectional"))
    )
    (net (code "229") (name "unconnected-(NAVP-PK2(ADC10{slash}PCINT18)-Pad87)") (class "Default")
      (node (ref "NAVP") (pin "87") (pinfunction "PK2(ADC10/PCINT18)_87") (pintype "bidirectional"))
    )
    (net (code "230") (name "unconnected-(NAVP-PK3(ADC11{slash}PCINT19)-Pad86)") (class "Default")
      (node (ref "NAVP") (pin "86") (pinfunction "PK3(ADC11/PCINT19)_86") (pintype "bidirectional"))
    )
    (net (code "231") (name "unconnected-(NAVP-PK4(ADC12{slash}PCINT20)-Pad85)") (class "Default")
      (node (ref "NAVP") (pin "85") (pinfunction "PK4(ADC12/PCINT20)_85") (pintype "bidirectional"))
    )
    (net (code "232") (name "unconnected-(NAVP-PK5(ADC13{slash}PCINT21)-Pad84)") (class "Default")
      (node (ref "NAVP") (pin "84") (pinfunction "PK5(ADC13/PCINT21)_84") (pintype "bidirectional"))
    )
    (net (code "233") (name "unconnected-(NAVP-PK6(ADC14{slash}PCINT22)-Pad83)") (class "Default")
      (node (ref "NAVP") (pin "83") (pinfunction "PK6(ADC14/PCINT22)_83") (pintype "bidirectional"))
    )
    (net (code "234") (name "unconnected-(NAVP-PK7(ADC15{slash}PCINT23)-Pad82)") (class "Default")
      (node (ref "NAVP") (pin "82") (pinfunction "PK7(ADC15/PCINT23)_82") (pintype "bidirectional"))
    )
    (net (code "235") (name "unconnected-(NAVP-PL0(ICP4)-Pad35)") (class "Default")
      (node (ref "NAVP") (pin "35") (pinfunction "PL0(ICP4)_35") (pintype "bidirectional"))
    )
    (net (code "236") (name "unconnected-(NAVP-PL1(ICP5)-Pad36)") (class "Default")
      (node (ref "NAVP") (pin "36") (pinfunction "PL1(ICP5)_36") (pintype "bidirectional"))
    )
    (net (code "237") (name "unconnected-(NAVP-PL2(T5)-Pad37)") (class "Default")
      (node (ref "NAVP") (pin "37") (pinfunction "PL2(T5)_37") (pintype "bidirectional"))
    )
    (net (code "238") (name "unconnected-(NAVP-PL3(OC5A)-Pad38)") (class "Default")
      (node (ref "NAVP") (pin "38") (pinfunction "PL3(OC5A)_38") (pintype "bidirectional"))
    )
    (net (code "239") (name "unconnected-(NAVP-PL4(OC5B)-Pad39)") (class "Default")
      (node (ref "NAVP") (pin "39") (pinfunction "PL4(OC5B)_39") (pintype "bidirectional"))
    )
    (net (code "240") (name "unconnected-(NAVP-PL5(OC5C)-Pad40)") (class "Default")
      (node (ref "NAVP") (pin "40") (pinfunction "PL5(OC5C)_40") (pintype "bidirectional"))
    )
    (net (code "241") (name "unconnected-(NAVP-PL6-Pad41)") (class "Default")
      (node (ref "NAVP") (pin "41") (pinfunction "PL6_41") (pintype "bidirectional"))
    )
    (net (code "242") (name "unconnected-(NAVP-PL7-Pad42)") (class "Default")
      (node (ref "NAVP") (pin "42") (pinfunction "PL7_42") (pintype "bidirectional"))
    )
    (net (code "243") (name "unconnected-(U$8-EOC-Pad2)") (class "Default")
      (node (ref "U$8") (pin "2") (pinfunction "EOC_2") (pintype "output"))
    )
    (net (code "244") (name "unconnected-(U$8-NC-Pad5)") (class "Default")
      (node (ref "U$8") (pin "5") (pinfunction "NC_5") (pintype "bidirectional"))
    )
    (net (code "245") (name "unconnected-(U$8-XCLR-Pad8)") (class "Default")
      (node (ref "U$8") (pin "8") (pinfunction "XCLR_8") (pintype "input"))
    )
    (net (code "246") (name "unconnected-(U4-AGND-Pad5)") (class "Default")
      (node (ref "U4") (pin "5") (pinfunction "AGND_5") (pintype "bidirectional"))
    )
    (net (code "247") (name "unconnected-(U4-AREF-Pad20)") (class "Default")
      (node (ref "U4") (pin "20") (pinfunction "AREF_20") (pintype "bidirectional"))
    )
    (net (code "248") (name "unconnected-(U4-AVCC-Pad18)") (class "Default")
      (node (ref "U4") (pin "18") (pinfunction "AVCC_18") (pintype "bidirectional"))
    )
    (net (code "249") (name "unconnected-(U4-GND-Pad3)") (class "Default")
      (node (ref "U4") (pin "3") (pinfunction "GND_3") (pintype "bidirectional"))
    )
    (net (code "250") (name "unconnected-(U4-GND-Pad21)") (class "Default")
      (node (ref "U4") (pin "21") (pinfunction "GND_21") (pintype "bidirectional"))
    )
    (net (code "251") (name "unconnected-(U4-PB0(ICP)-Pad12)") (class "Default")
      (node (ref "U4") (pin "12") (pinfunction "PB0(ICP)_12") (pintype "bidirectional"))
    )
    (net (code "252") (name "unconnected-(U4-PB1(OC1A)-Pad13)") (class "Default")
      (node (ref "U4") (pin "13") (pinfunction "PB1(OC1A)_13") (pintype "bidirectional"))
    )
    (net (code "253") (name "unconnected-(U4-PB2(SS{slash}OC1B)-Pad14)") (class "Default")
      (node (ref "U4") (pin "14") (pinfunction "PB2(SS/OC1B)_14") (pintype "bidirectional"))
    )
    (net (code "254") (name "unconnected-(U4-PB3(MOSI{slash}OC2)-Pad15)") (class "Default")
      (node (ref "U4") (pin "15") (pinfunction "PB3(MOSI/OC2)_15") (pintype "bidirectional"))
    )
    (net (code "255") (name "unconnected-(U4-PB4(MISO)-Pad16)") (class "Default")
      (node (ref "U4") (pin "16") (pinfunction "PB4(MISO)_16") (pintype "bidirectional"))
    )
    (net (code "256") (name "unconnected-(U4-PB5(SCK)-Pad17)") (class "Default")
      (node (ref "U4") (pin "17") (pinfunction "PB5(SCK)_17") (pintype "bidirectional"))
    )
    (net (code "257") (name "unconnected-(U4-PD0(RXD)-Pad30)") (class "Default")
      (node (ref "U4") (pin "30") (pinfunction "PD0(RXD)_30") (pintype "bidirectional"))
    )
    (net (code "258") (name "unconnected-(U4-PD1(TXD)-Pad31)") (class "Default")
      (node (ref "U4") (pin "31") (pinfunction "PD1(TXD)_31") (pintype "bidirectional"))
    )
    (net (code "259") (name "unconnected-(U4-PD3(INT1)-Pad1)") (class "Default")
      (node (ref "U4") (pin "1") (pinfunction "PD3(INT1)_1") (pintype "bidirectional"))
    )
    (net (code "260") (name "unconnected-(U4-PD4(XCK{slash}T0)-Pad2)") (class "Default")
      (node (ref "U4") (pin "2") (pinfunction "PD4(XCK/T0)_2") (pintype "bidirectional"))
    )
    (net (code "261") (name "unconnected-(U4-PD5(T1)-Pad9)") (class "Default")
      (node (ref "U4") (pin "9") (pinfunction "PD5(T1)_9") (pintype "bidirectional"))
    )
    (net (code "262") (name "unconnected-(U4-PD6(AIN0)-Pad10)") (class "Default")
      (node (ref "U4") (pin "10") (pinfunction "PD6(AIN0)_10") (pintype "bidirectional"))
    )
    (net (code "263") (name "unconnected-(U4-PD7(AIN1)-Pad11)") (class "Default")
      (node (ref "U4") (pin "11") (pinfunction "PD7(AIN1)_11") (pintype "bidirectional"))
    )
    (net (code "264") (name "unconnected-(U4-VCC-Pad4)") (class "Default")
      (node (ref "U4") (pin "4") (pinfunction "VCC_4") (pintype "bidirectional"))
    )
    (net (code "265") (name "unconnected-(U4-VCC-Pad6)") (class "Default")
      (node (ref "U4") (pin "6") (pinfunction "VCC_6") (pintype "bidirectional"))
    )
    (net (code "266") (name "unconnected-(U5-AD0-Pad9)") (class "Default")
      (node (ref "U5") (pin "9") (pinfunction "AD0_9") (pintype "bidirectional"))
    )
    (net (code "267") (name "unconnected-(U5-CLKIN-Pad1)") (class "Default")
      (node (ref "U5") (pin "1") (pinfunction "CLKIN_1") (pintype "bidirectional"))
    )
    (net (code "268") (name "unconnected-(U5-CPOUT-Pad20)") (class "Default")
      (node (ref "U5") (pin "20") (pinfunction "CPOUT_20") (pintype "bidirectional"))
    )
    (net (code "269") (name "unconnected-(U5-INT-Pad12)") (class "Default")
      (node (ref "U5") (pin "12") (pinfunction "INT_12") (pintype "bidirectional"))
    )
    (net (code "270") (name "unconnected-(U5-REGOUT-Pad10)") (class "Default")
      (node (ref "U5") (pin "10") (pinfunction "REGOUT_10") (pintype "bidirectional"))
    )
    (net (code "271") (name "unconnected-(U5-RESV-G-Pad11)") (class "Default")
      (node (ref "U5") (pin "11") (pinfunction "RESV-G_11") (pintype "bidirectional"))
    )
    (net (code "272") (name "unconnected-(U6-CS-Pad7)") (class "Default")
      (node (ref "U6") (pin "7") (pinfunction "CS_7") (pintype "bidirectional"))
    )
    (net (code "273") (name "unconnected-(U6-INT1-Pad8)") (class "Default")
      (node (ref "U6") (pin "8") (pinfunction "INT1_8") (pintype "bidirectional"))
    )
    (net (code "274") (name "unconnected-(U6-INT2-Pad9)") (class "Default")
      (node (ref "U6") (pin "9") (pinfunction "INT2_9") (pintype "bidirectional"))
    )
    (net (code "275") (name "unconnected-(U6-NC-Pad3)") (class "Default")
      (node (ref "U6") (pin "3") (pinfunction "NC_3") (pintype "bidirectional"))
    )
    (net (code "276") (name "unconnected-(U6-NC-Pad10)") (class "Default")
      (node (ref "U6") (pin "10") (pinfunction "NC_10") (pintype "bidirectional"))
    )
    (net (code "277") (name "unconnected-(U6-NC-Pad11)") (class "Default")
      (node (ref "U6") (pin "11") (pinfunction "NC_11") (pintype "bidirectional"))
    )
    (net (code "278") (name "unconnected-(U6-SDO-Pad12)") (class "Default")
      (node (ref "U6") (pin "12") (pinfunction "SDO_12") (pintype "bidirectional"))
    )
    (net (code "279") (name "unconnected-(U8-INT1-Pad26)") (class "Default")
      (node (ref "U8") (pin "26") (pinfunction "INT1_26") (pintype "bidirectional"))
    )
    (net (code "280") (name "unconnected-(U8-INT2-Pad27)") (class "Default")
      (node (ref "U8") (pin "27") (pinfunction "INT2_27") (pintype "bidirectional"))
    )
  )
)
